# RF08b.net
KiCad netlist of a schematic drawn in EAGLE
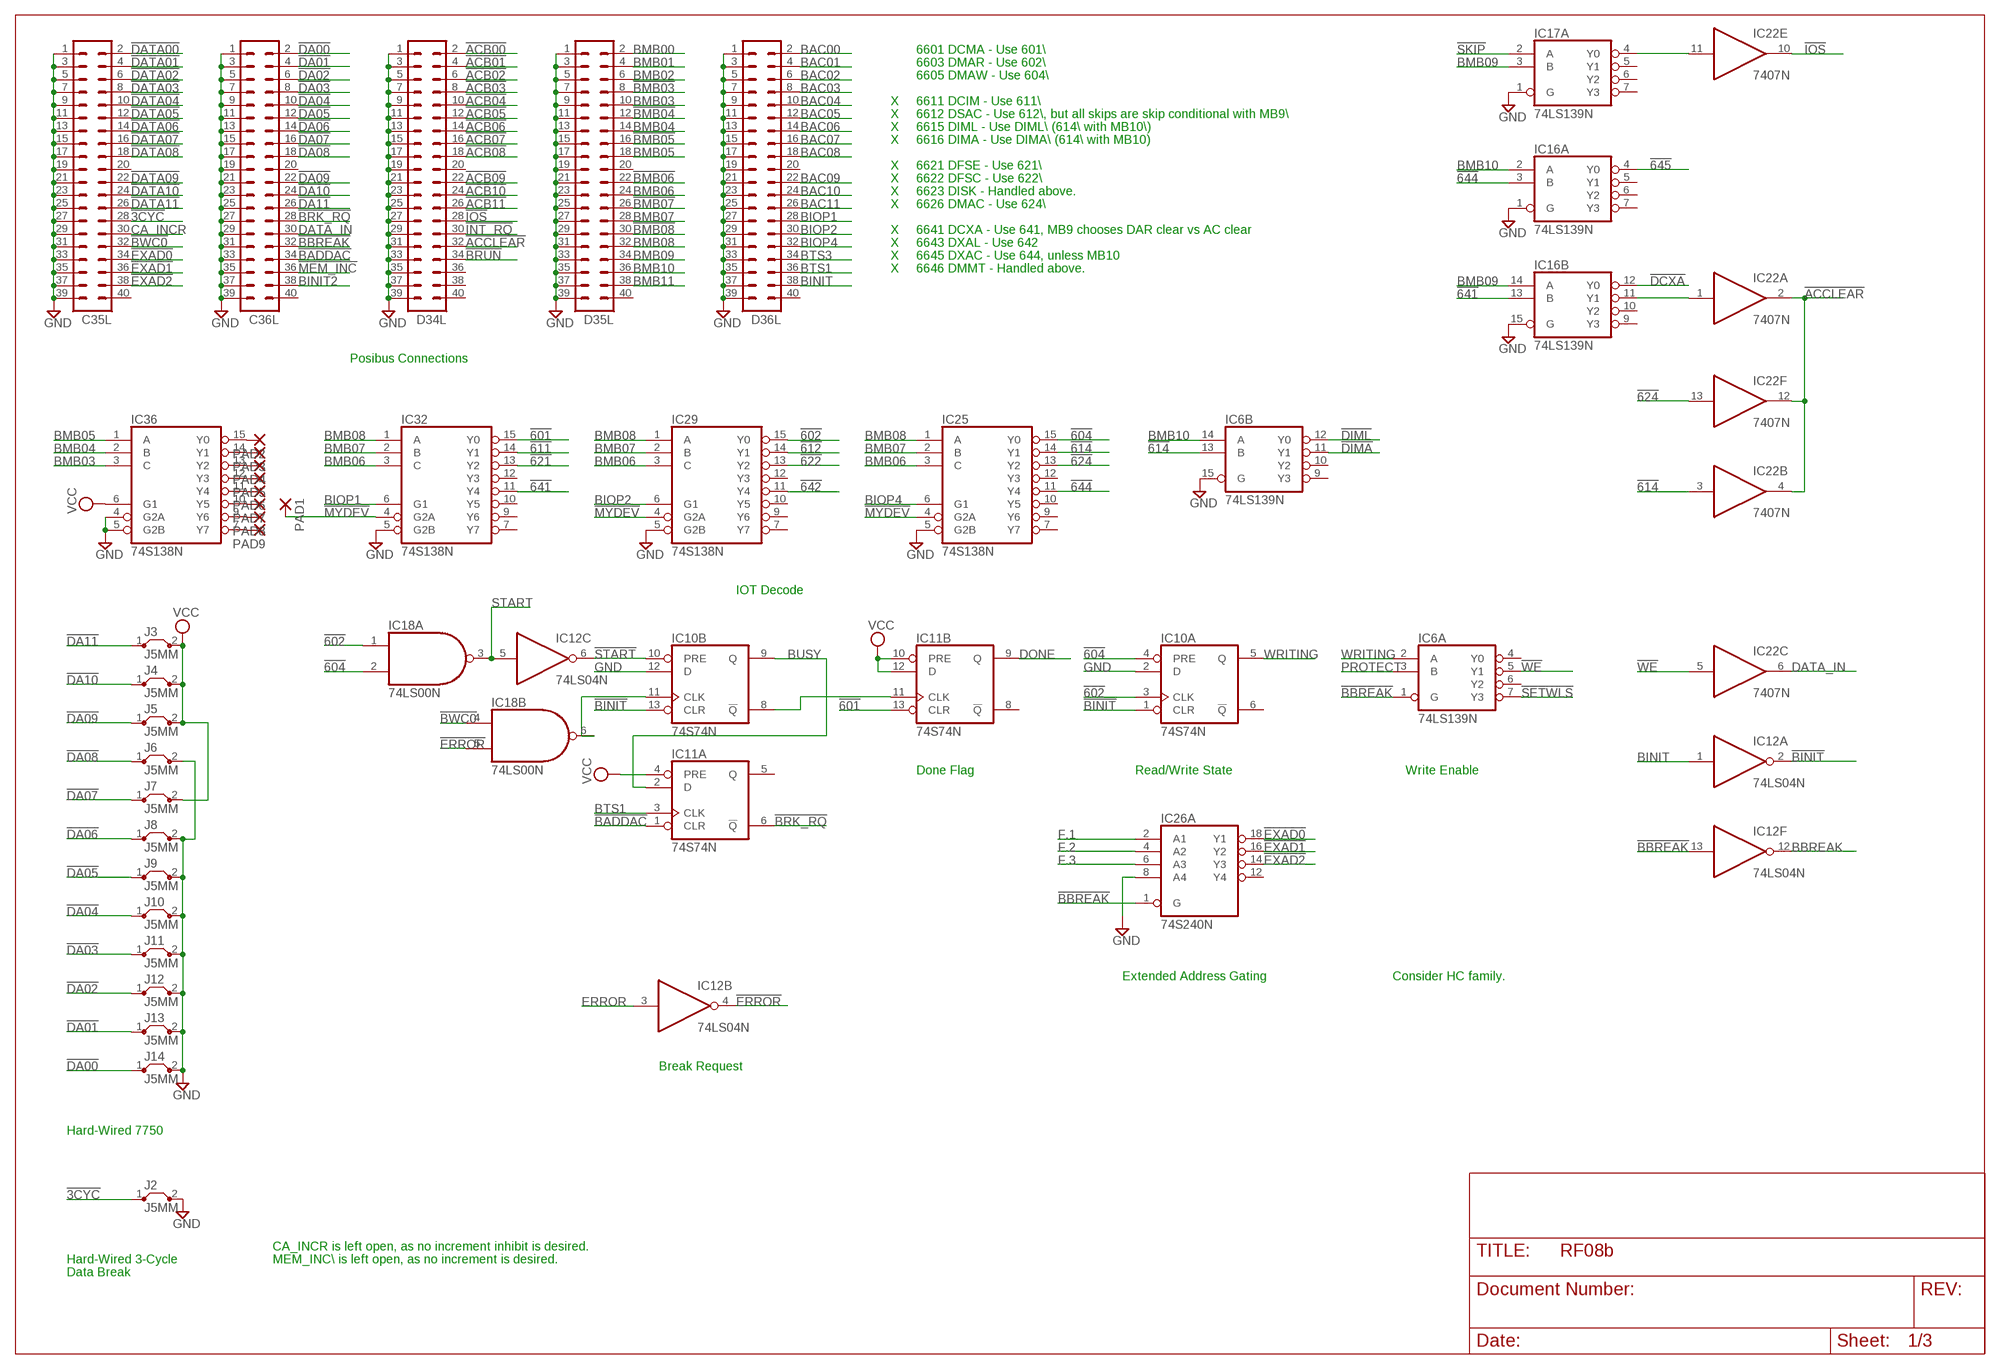
[diagram p0: schematic, sheet 1]
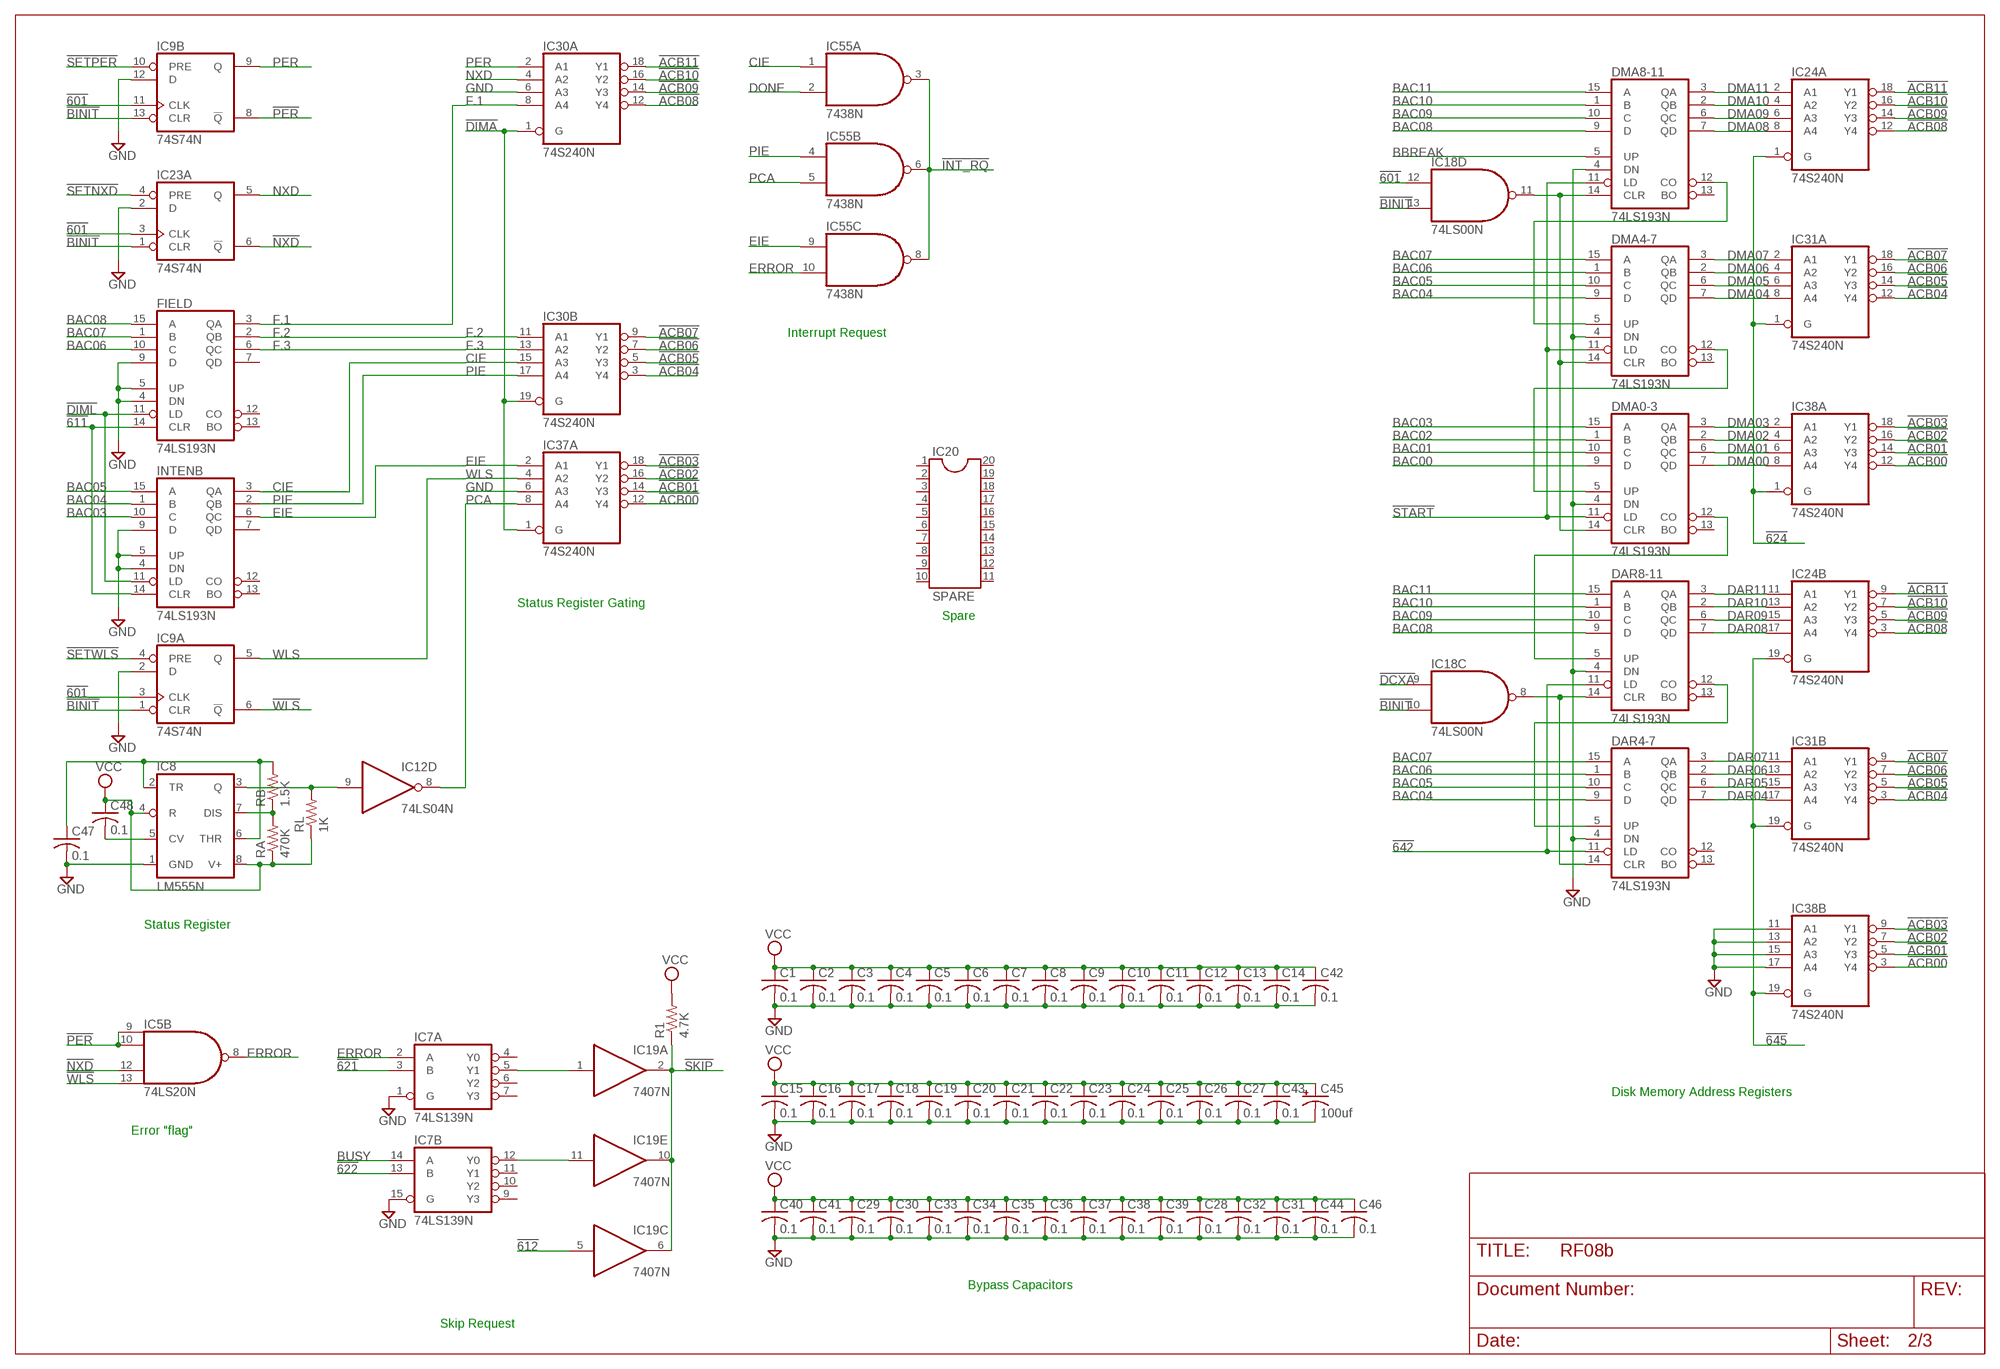
[diagram p1: schematic, sheet 2]
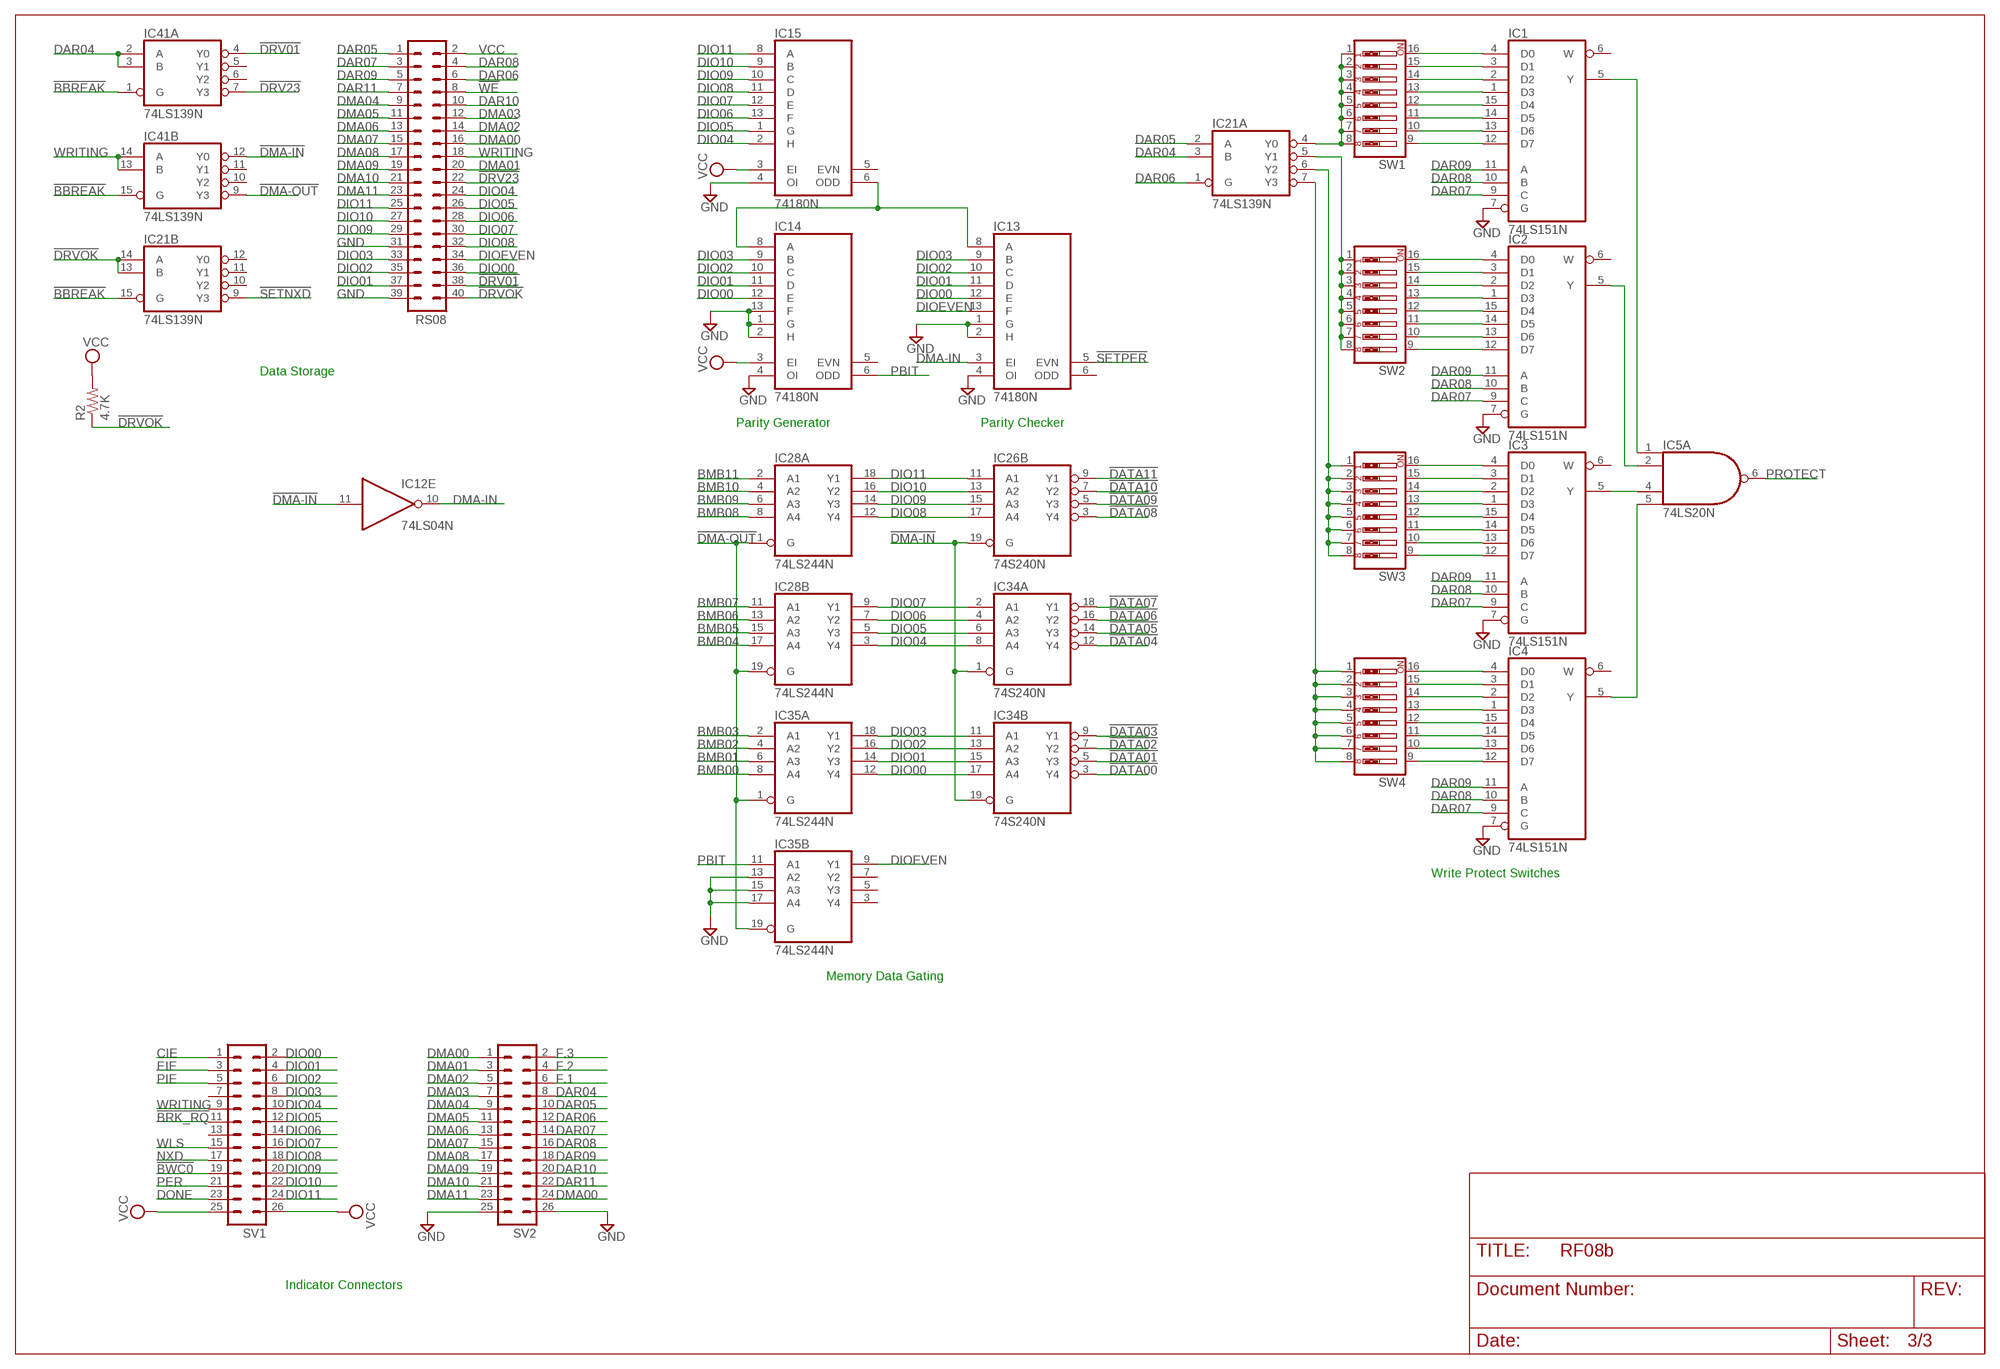
[diagram p2: schematic, sheet 3]

(export (version "E")
  (design (tool "Eeschema 10.0.6"))
  (components
    (comp (ref "C35L")
      (value "MA20-2")
      (footprint "eagle-import:MA20-2")
      (libsource (lib "eagle-import") (part "MA20-2"))
    )
    (comp (ref "C36L")
      (value "MA20-2")
      (footprint "eagle-import:MA20-2")
      (libsource (lib "eagle-import") (part "MA20-2"))
    )
    (comp (ref "D34L")
      (value "MA20-2")
      (footprint "eagle-import:MA20-2")
      (libsource (lib "eagle-import") (part "MA20-2"))
    )
    (comp (ref "D35L")
      (value "MA20-2")
      (footprint "eagle-import:MA20-2")
      (libsource (lib "eagle-import") (part "MA20-2"))
    )
    (comp (ref "D36L")
      (value "MA20-2")
      (footprint "eagle-import:MA20-2")
      (libsource (lib "eagle-import") (part "MA20-2"))
    )
    (comp (ref "IC6")
      (value "74LS139N")
      (footprint "eagle-import:DIL16")
      (libsource (lib "eagle-import") (part "74139NS"))
    )
    (comp (ref "IC10")
      (value "74S74N")
      (footprint "eagle-import:DIL14")
      (libsource (lib "eagle-import") (part "7474NS"))
    )
    (comp (ref "IC11")
      (value "74S74N")
      (footprint "eagle-import:DIL14")
      (libsource (lib "eagle-import") (part "7474NS"))
    )
    (comp (ref "IC12")
      (value "74LS04N")
      (footprint "eagle-import:DIL14")
      (libsource (lib "eagle-import") (part "7404NLS"))
    )
    (comp (ref "IC16")
      (value "74LS139N")
      (footprint "eagle-import:DIL16")
      (libsource (lib "eagle-import") (part "74139NS"))
    )
    (comp (ref "IC17")
      (value "74LS139N")
      (footprint "eagle-import:DIL16")
      (libsource (lib "eagle-import") (part "74139NS"))
    )
    (comp (ref "IC18")
      (value "74LS00N")
      (footprint "eagle-import:DIL14")
      (libsource (lib "eagle-import") (part "7400NLS"))
    )
    (comp (ref "IC22")
      (value "7407N")
      (footprint "eagle-import:DIL14")
      (libsource (lib "eagle-import") (part "7407N"))
    )
    (comp (ref "IC25")
      (value "74S138N")
      (footprint "eagle-import:DIL16")
      (libsource (lib "eagle-import") (part "74138NS"))
    )
    (comp (ref "IC26")
      (value "74S240N")
      (footprint "eagle-import:DIL20")
      (libsource (lib "eagle-import") (part "74240NS"))
    )
    (comp (ref "IC29")
      (value "74S138N")
      (footprint "eagle-import:DIL16")
      (libsource (lib "eagle-import") (part "74138NS"))
    )
    (comp (ref "IC32")
      (value "74S138N")
      (footprint "eagle-import:DIL16")
      (libsource (lib "eagle-import") (part "74138NS"))
    )
    (comp (ref "IC36")
      (value "74S138N")
      (footprint "eagle-import:DIL16")
      (libsource (lib "eagle-import") (part "74138NS"))
    )
    (comp (ref "J2")
      (value "J5MM")
      (footprint "eagle-import:05")
      (libsource (lib "eagle-import") (part "J5MM"))
    )
    (comp (ref "J3")
      (value "J5MM")
      (footprint "eagle-import:05")
      (libsource (lib "eagle-import") (part "J5MM"))
    )
    (comp (ref "J4")
      (value "J5MM")
      (footprint "eagle-import:05")
      (libsource (lib "eagle-import") (part "J5MM"))
    )
    (comp (ref "J5")
      (value "J5MM")
      (footprint "eagle-import:05")
      (libsource (lib "eagle-import") (part "J5MM"))
    )
    (comp (ref "J6")
      (value "J5MM")
      (footprint "eagle-import:05")
      (libsource (lib "eagle-import") (part "J5MM"))
    )
    (comp (ref "J7")
      (value "J5MM")
      (footprint "eagle-import:05")
      (libsource (lib "eagle-import") (part "J5MM"))
    )
    (comp (ref "J8")
      (value "J5MM")
      (footprint "eagle-import:05")
      (libsource (lib "eagle-import") (part "J5MM"))
    )
    (comp (ref "J9")
      (value "J5MM")
      (footprint "eagle-import:05")
      (libsource (lib "eagle-import") (part "J5MM"))
    )
    (comp (ref "J10")
      (value "J5MM")
      (footprint "eagle-import:05")
      (libsource (lib "eagle-import") (part "J5MM"))
    )
    (comp (ref "J11")
      (value "J5MM")
      (footprint "eagle-import:05")
      (libsource (lib "eagle-import") (part "J5MM"))
    )
    (comp (ref "J12")
      (value "J5MM")
      (footprint "eagle-import:05")
      (libsource (lib "eagle-import") (part "J5MM"))
    )
    (comp (ref "J13")
      (value "J5MM")
      (footprint "eagle-import:05")
      (libsource (lib "eagle-import") (part "J5MM"))
    )
    (comp (ref "J14")
      (value "J5MM")
      (footprint "eagle-import:05")
      (libsource (lib "eagle-import") (part "J5MM"))
    )
    (comp (ref "PAD1")
      (value "1,6/0,8")
      (footprint "eagle-import:1,6_0,8")
      (libsource (lib "eagle-import") (part "1,6/0,8"))
    )
    (comp (ref "PAD2")
      (value "1,6/0,8")
      (footprint "eagle-import:1,6_0,8")
      (libsource (lib "eagle-import") (part "1,6/0,8"))
    )
    (comp (ref "PAD3")
      (value "1,6/0,8")
      (footprint "eagle-import:1,6_0,8")
      (libsource (lib "eagle-import") (part "1,6/0,8"))
    )
    (comp (ref "PAD4")
      (value "1,6/0,8")
      (footprint "eagle-import:1,6_0,8")
      (libsource (lib "eagle-import") (part "1,6/0,8"))
    )
    (comp (ref "PAD5")
      (value "1,6/0,8")
      (footprint "eagle-import:1,6_0,8")
      (libsource (lib "eagle-import") (part "1,6/0,8"))
    )
    (comp (ref "PAD6")
      (value "1,6/0,8")
      (footprint "eagle-import:1,6_0,8")
      (libsource (lib "eagle-import") (part "1,6/0,8"))
    )
    (comp (ref "PAD7")
      (value "1,6/0,8")
      (footprint "eagle-import:1,6_0,8")
      (libsource (lib "eagle-import") (part "1,6/0,8"))
    )
    (comp (ref "PAD8")
      (value "1,6/0,8")
      (footprint "eagle-import:1,6_0,8")
      (libsource (lib "eagle-import") (part "1,6/0,8"))
    )
    (comp (ref "PAD9")
      (value "1,6/0,8")
      (footprint "eagle-import:1,6_0,8")
      (libsource (lib "eagle-import") (part "1,6/0,8"))
    )
    (comp (ref "C1")
      (value "0.1")
      (footprint "eagle-import:C050-025X075")
      (libsource (lib "eagle-import") (part "C-US050-025X075"))
    )
    (comp (ref "C2")
      (value "0.1")
      (footprint "eagle-import:C050-025X075")
      (libsource (lib "eagle-import") (part "C-US050-025X075"))
    )
    (comp (ref "C3")
      (value "0.1")
      (footprint "eagle-import:C050-025X075")
      (libsource (lib "eagle-import") (part "C-US050-025X075"))
    )
    (comp (ref "C4")
      (value "0.1")
      (footprint "eagle-import:C050-025X075")
      (libsource (lib "eagle-import") (part "C-US050-025X075"))
    )
    (comp (ref "C5")
      (value "0.1")
      (footprint "eagle-import:C050-025X075")
      (libsource (lib "eagle-import") (part "C-US050-025X075"))
    )
    (comp (ref "C6")
      (value "0.1")
      (footprint "eagle-import:C050-025X075")
      (libsource (lib "eagle-import") (part "C-US050-025X075"))
    )
    (comp (ref "C7")
      (value "0.1")
      (footprint "eagle-import:C050-025X075")
      (libsource (lib "eagle-import") (part "C-US050-025X075"))
    )
    (comp (ref "C8")
      (value "0.1")
      (footprint "eagle-import:C050-025X075")
      (libsource (lib "eagle-import") (part "C-US050-025X075"))
    )
    (comp (ref "C9")
      (value "0.1")
      (footprint "eagle-import:C050-025X075")
      (libsource (lib "eagle-import") (part "C-US050-025X075"))
    )
    (comp (ref "C10")
      (value "0.1")
      (footprint "eagle-import:C050-025X075")
      (libsource (lib "eagle-import") (part "C-US050-025X075"))
    )
    (comp (ref "C11")
      (value "0.1")
      (footprint "eagle-import:C050-025X075")
      (libsource (lib "eagle-import") (part "C-US050-025X075"))
    )
    (comp (ref "C12")
      (value "0.1")
      (footprint "eagle-import:C050-025X075")
      (libsource (lib "eagle-import") (part "C-US050-025X075"))
    )
    (comp (ref "C13")
      (value "0.1")
      (footprint "eagle-import:C050-025X075")
      (libsource (lib "eagle-import") (part "C-US050-025X075"))
    )
    (comp (ref "C14")
      (value "0.1")
      (footprint "eagle-import:C050-025X075")
      (libsource (lib "eagle-import") (part "C-US050-025X075"))
    )
    (comp (ref "C15")
      (value "0.1")
      (footprint "eagle-import:C050-025X075")
      (libsource (lib "eagle-import") (part "C-US050-025X075"))
    )
    (comp (ref "C16")
      (value "0.1")
      (footprint "eagle-import:C050-025X075")
      (libsource (lib "eagle-import") (part "C-US050-025X075"))
    )
    (comp (ref "C17")
      (value "0.1")
      (footprint "eagle-import:C050-025X075")
      (libsource (lib "eagle-import") (part "C-US050-025X075"))
    )
    (comp (ref "C18")
      (value "0.1")
      (footprint "eagle-import:C050-025X075")
      (libsource (lib "eagle-import") (part "C-US050-025X075"))
    )
    (comp (ref "C19")
      (value "0.1")
      (footprint "eagle-import:C050-025X075")
      (libsource (lib "eagle-import") (part "C-US050-025X075"))
    )
    (comp (ref "C20")
      (value "0.1")
      (footprint "eagle-import:C050-025X075")
      (libsource (lib "eagle-import") (part "C-US050-025X075"))
    )
    (comp (ref "C21")
      (value "0.1")
      (footprint "eagle-import:C050-025X075")
      (libsource (lib "eagle-import") (part "C-US050-025X075"))
    )
    (comp (ref "C22")
      (value "0.1")
      (footprint "eagle-import:C050-025X075")
      (libsource (lib "eagle-import") (part "C-US050-025X075"))
    )
    (comp (ref "C23")
      (value "0.1")
      (footprint "eagle-import:C050-025X075")
      (libsource (lib "eagle-import") (part "C-US050-025X075"))
    )
    (comp (ref "C24")
      (value "0.1")
      (footprint "eagle-import:C050-025X075")
      (libsource (lib "eagle-import") (part "C-US050-025X075"))
    )
    (comp (ref "C25")
      (value "0.1")
      (footprint "eagle-import:C050-025X075")
      (libsource (lib "eagle-import") (part "C-US050-025X075"))
    )
    (comp (ref "C26")
      (value "0.1")
      (footprint "eagle-import:C050-025X075")
      (libsource (lib "eagle-import") (part "C-US050-025X075"))
    )
    (comp (ref "C27")
      (value "0.1")
      (footprint "eagle-import:C050-025X075")
      (libsource (lib "eagle-import") (part "C-US050-025X075"))
    )
    (comp (ref "C28")
      (value "0.1")
      (footprint "eagle-import:C050-025X075")
      (libsource (lib "eagle-import") (part "C-US050-025X075"))
    )
    (comp (ref "C29")
      (value "0.1")
      (footprint "eagle-import:C050-025X075")
      (libsource (lib "eagle-import") (part "C-US050-025X075"))
    )
    (comp (ref "C30")
      (value "0.1")
      (footprint "eagle-import:C050-025X075")
      (libsource (lib "eagle-import") (part "C-US050-025X075"))
    )
    (comp (ref "C31")
      (value "0.1")
      (footprint "eagle-import:C050-025X075")
      (libsource (lib "eagle-import") (part "C-US050-025X075"))
    )
    (comp (ref "C32")
      (value "0.1")
      (footprint "eagle-import:C050-025X075")
      (libsource (lib "eagle-import") (part "C-US050-025X075"))
    )
    (comp (ref "C33")
      (value "0.1")
      (footprint "eagle-import:C050-025X075")
      (libsource (lib "eagle-import") (part "C-US050-025X075"))
    )
    (comp (ref "C34")
      (value "0.1")
      (footprint "eagle-import:C050-025X075")
      (libsource (lib "eagle-import") (part "C-US050-025X075"))
    )
    (comp (ref "C35")
      (value "0.1")
      (footprint "eagle-import:C050-025X075")
      (libsource (lib "eagle-import") (part "C-US050-025X075"))
    )
    (comp (ref "C36")
      (value "0.1")
      (footprint "eagle-import:C050-025X075")
      (libsource (lib "eagle-import") (part "C-US050-025X075"))
    )
    (comp (ref "C37")
      (value "0.1")
      (footprint "eagle-import:C050-025X075")
      (libsource (lib "eagle-import") (part "C-US050-025X075"))
    )
    (comp (ref "C38")
      (value "0.1")
      (footprint "eagle-import:C050-025X075")
      (libsource (lib "eagle-import") (part "C-US050-025X075"))
    )
    (comp (ref "C39")
      (value "0.1")
      (footprint "eagle-import:C050-025X075")
      (libsource (lib "eagle-import") (part "C-US050-025X075"))
    )
    (comp (ref "C40")
      (value "0.1")
      (footprint "eagle-import:C050-025X075")
      (libsource (lib "eagle-import") (part "C-US050-025X075"))
    )
    (comp (ref "C41")
      (value "0.1")
      (footprint "eagle-import:C050-025X075")
      (libsource (lib "eagle-import") (part "C-US050-025X075"))
    )
    (comp (ref "C42")
      (value "0.1")
      (footprint "eagle-import:C050-025X075")
      (libsource (lib "eagle-import") (part "C-US050-025X075"))
    )
    (comp (ref "C43")
      (value "0.1")
      (footprint "eagle-import:C050-025X075")
      (libsource (lib "eagle-import") (part "C-US050-025X075"))
    )
    (comp (ref "C44")
      (value "0.1")
      (footprint "eagle-import:C050-025X075")
      (libsource (lib "eagle-import") (part "C-US050-025X075"))
    )
    (comp (ref "C45")
      (value "100uf")
      (footprint "eagle-import:E22-6")
      (libsource (lib "eagle-import") (part "CPOL-USE22-6AXIAL"))
    )
    (comp (ref "C46")
      (value "0.1")
      (footprint "eagle-import:C050-025X075")
      (libsource (lib "eagle-import") (part "C-US050-025X075"))
    )
    (comp (ref "C47")
      (value "0.1")
      (footprint "eagle-import:C050-025X075")
      (libsource (lib "eagle-import") (part "C-US050-025X075"))
    )
    (comp (ref "C48")
      (value "0.1")
      (footprint "eagle-import:C050-025X075")
      (libsource (lib "eagle-import") (part "C-US050-025X075"))
    )
    (comp (ref "DAR4-7")
      (value "74LS193N")
      (footprint "eagle-import:DIL16")
      (libsource (lib "eagle-import") (part "74192NLS"))
    )
    (comp (ref "DAR8-11")
      (value "74LS193N")
      (footprint "eagle-import:DIL16")
      (libsource (lib "eagle-import") (part "74192NLS"))
    )
    (comp (ref "DMA0-3")
      (value "74LS193N")
      (footprint "eagle-import:DIL16")
      (libsource (lib "eagle-import") (part "74192NLS"))
    )
    (comp (ref "DMA4-7")
      (value "74LS193N")
      (footprint "eagle-import:DIL16")
      (libsource (lib "eagle-import") (part "74192NLS"))
    )
    (comp (ref "DMA8-11")
      (value "74LS193N")
      (footprint "eagle-import:DIL16")
      (libsource (lib "eagle-import") (part "74192NLS"))
    )
    (comp (ref "FIELD")
      (value "74LS193N")
      (footprint "eagle-import:DIL16")
      (libsource (lib "eagle-import") (part "74192NLS"))
    )
    (comp (ref "IC5")
      (value "74LS20N")
      (footprint "eagle-import:DIL14")
      (libsource (lib "eagle-import") (part "7420NLS"))
    )
    (comp (ref "IC7")
      (value "74LS139N")
      (footprint "eagle-import:DIL16")
      (libsource (lib "eagle-import") (part "74139NLS"))
    )
    (comp (ref "IC8")
      (value "LM555N")
      (footprint "eagle-import:DIL08")
      (libsource (lib "eagle-import") (part "555NLM"))
    )
    (comp (ref "IC9")
      (value "74S74N")
      (footprint "eagle-import:DIL14")
      (libsource (lib "eagle-import") (part "7474NS"))
    )
    (comp (ref "IC19")
      (value "7407N")
      (footprint "eagle-import:DIL14")
      (libsource (lib "eagle-import") (part "7407N"))
    )
    (comp (ref "IC20")
      (value "SPARE")
      (footprint "eagle-import:DIL20")
      (libsource (lib "eagle-import") (part "DIL20"))
    )
    (comp (ref "IC23")
      (value "74S74N")
      (footprint "eagle-import:DIL14")
      (libsource (lib "eagle-import") (part "7474NS"))
    )
    (comp (ref "IC24")
      (value "74S240N")
      (footprint "eagle-import:DIL20")
      (libsource (lib "eagle-import") (part "74240NS"))
    )
    (comp (ref "IC30")
      (value "74S240N")
      (footprint "eagle-import:DIL20")
      (libsource (lib "eagle-import") (part "74240NS"))
    )
    (comp (ref "IC31")
      (value "74S240N")
      (footprint "eagle-import:DIL20")
      (libsource (lib "eagle-import") (part "74240NS"))
    )
    (comp (ref "IC37")
      (value "74S240N")
      (footprint "eagle-import:DIL20")
      (libsource (lib "eagle-import") (part "74240NS"))
    )
    (comp (ref "IC38")
      (value "74S240N")
      (footprint "eagle-import:DIL20")
      (libsource (lib "eagle-import") (part "74240NS"))
    )
    (comp (ref "IC55")
      (value "7438N")
      (footprint "eagle-import:DIL14")
      (libsource (lib "eagle-import") (part "7438N"))
    )
    (comp (ref "INTENB")
      (value "74LS193N")
      (footprint "eagle-import:DIL16")
      (libsource (lib "eagle-import") (part "74192NLS"))
    )
    (comp (ref "R1")
      (value "4.7K")
      (footprint "eagle-import:0207_10")
      (libsource (lib "eagle-import") (part "R-US_0207/10"))
    )
    (comp (ref "RA")
      (value "470K")
      (footprint "eagle-import:0207_10")
      (libsource (lib "eagle-import") (part "R-US_0207/10"))
    )
    (comp (ref "RB")
      (value "1.5K")
      (footprint "eagle-import:0207_10")
      (libsource (lib "eagle-import") (part "R-US_0207/10"))
    )
    (comp (ref "RL")
      (value "1K")
      (footprint "eagle-import:0207_10")
      (libsource (lib "eagle-import") (part "R-US_0207/10"))
    )
    (comp (ref "IC1")
      (value "74LS151N")
      (footprint "eagle-import:DIL16")
      (libsource (lib "eagle-import") (part "74151NLS"))
    )
    (comp (ref "IC2")
      (value "74LS151N")
      (footprint "eagle-import:DIL16")
      (libsource (lib "eagle-import") (part "74151NLS"))
    )
    (comp (ref "IC3")
      (value "74LS151N")
      (footprint "eagle-import:DIL16")
      (libsource (lib "eagle-import") (part "74151NLS"))
    )
    (comp (ref "IC4")
      (value "74LS151N")
      (footprint "eagle-import:DIL16")
      (libsource (lib "eagle-import") (part "74151NLS"))
    )
    (comp (ref "IC13")
      (value "74180N")
      (footprint "eagle-import:DIL14")
      (libsource (lib "eagle-import") (part "74180N"))
    )
    (comp (ref "IC14")
      (value "74180N")
      (footprint "eagle-import:DIL14")
      (libsource (lib "eagle-import") (part "74180N"))
    )
    (comp (ref "IC15")
      (value "74180N")
      (footprint "eagle-import:DIL14")
      (libsource (lib "eagle-import") (part "74180N"))
    )
    (comp (ref "IC21")
      (value "74LS139N")
      (footprint "eagle-import:DIL16")
      (libsource (lib "eagle-import") (part "74139NLS"))
    )
    (comp (ref "IC28")
      (value "74LS244N")
      (footprint "eagle-import:DIL20")
      (libsource (lib "eagle-import") (part "74244NLS"))
    )
    (comp (ref "IC34")
      (value "74S240N")
      (footprint "eagle-import:DIL20")
      (libsource (lib "eagle-import") (part "74240NS"))
    )
    (comp (ref "IC35")
      (value "74LS244N")
      (footprint "eagle-import:DIL20")
      (libsource (lib "eagle-import") (part "74244NLS"))
    )
    (comp (ref "IC41")
      (value "74LS139N")
      (footprint "eagle-import:DIL16")
      (libsource (lib "eagle-import") (part "74139NLS"))
    )
    (comp (ref "R2")
      (value "4.7K")
      (footprint "eagle-import:0207_10")
      (libsource (lib "eagle-import") (part "R-US_0207/10"))
    )
    (comp (ref "RS08")
      (value "MA20-2")
      (footprint "eagle-import:MA20-2")
      (libsource (lib "eagle-import") (part "MA20-2"))
    )
    (comp (ref "SV1")
      (value "MA13-2")
      (footprint "eagle-import:MA13-2")
      (libsource (lib "eagle-import") (part "MA13-2"))
    )
    (comp (ref "SV2")
      (value "MA13-2")
      (footprint "eagle-import:MA13-2")
      (libsource (lib "eagle-import") (part "MA13-2"))
    )
    (comp (ref "SW1")
      (value "SW_DIP-8")
      (footprint "eagle-import:EDG-08")
      (libsource (lib "eagle-import") (part "SW_DIP-8"))
    )
    (comp (ref "SW2")
      (value "SW_DIP-8")
      (footprint "eagle-import:EDG-08")
      (libsource (lib "eagle-import") (part "SW_DIP-8"))
    )
    (comp (ref "SW3")
      (value "SW_DIP-8")
      (footprint "eagle-import:EDG-08")
      (libsource (lib "eagle-import") (part "SW_DIP-8"))
    )
    (comp (ref "SW4")
      (value "SW_DIP-8")
      (footprint "eagle-import:EDG-08")
      (libsource (lib "eagle-import") (part "SW_DIP-8"))
    )
  )
  (nets
    (net (code "1") (name "BAC00") (class "Default")
      (node (ref "D36L") (pin "2") (pinfunction "2_2") (pintype "passive"))
      (node (ref "DMA0-3") (pin "9") (pinfunction "D_9") (pintype "input"))
    )
    (net (code "2") (name "BAC01") (class "Default")
      (node (ref "D36L") (pin "4") (pinfunction "4_4") (pintype "passive"))
      (node (ref "DMA0-3") (pin "10") (pinfunction "C_10") (pintype "input"))
    )
    (net (code "3") (name "BAC02") (class "Default")
      (node (ref "D36L") (pin "6") (pinfunction "6_6") (pintype "passive"))
      (node (ref "DMA0-3") (pin "1") (pinfunction "B_1") (pintype "input"))
    )
    (net (code "4") (name "BAC03") (class "Default")
      (node (ref "D36L") (pin "8") (pinfunction "8_8") (pintype "passive"))
      (node (ref "DMA0-3") (pin "15") (pinfunction "A_15") (pintype "input"))
      (node (ref "INTENB") (pin "10") (pinfunction "C_10") (pintype "input"))
    )
    (net (code "5") (name "BAC04") (class "Default")
      (node (ref "D36L") (pin "10") (pinfunction "10_10") (pintype "passive"))
      (node (ref "DAR4-7") (pin "9") (pinfunction "D_9") (pintype "input"))
      (node (ref "DMA4-7") (pin "9") (pinfunction "D_9") (pintype "input"))
      (node (ref "INTENB") (pin "1") (pinfunction "B_1") (pintype "input"))
    )
    (net (code "6") (name "BAC05") (class "Default")
      (node (ref "D36L") (pin "12") (pinfunction "12_12") (pintype "passive"))
      (node (ref "DAR4-7") (pin "10") (pinfunction "C_10") (pintype "input"))
      (node (ref "DMA4-7") (pin "10") (pinfunction "C_10") (pintype "input"))
      (node (ref "INTENB") (pin "15") (pinfunction "A_15") (pintype "input"))
    )
    (net (code "7") (name "BAC06") (class "Default")
      (node (ref "D36L") (pin "14") (pinfunction "14_14") (pintype "passive"))
      (node (ref "DAR4-7") (pin "1") (pinfunction "B_1") (pintype "input"))
      (node (ref "DMA4-7") (pin "1") (pinfunction "B_1") (pintype "input"))
      (node (ref "FIELD") (pin "10") (pinfunction "C_10") (pintype "input"))
    )
    (net (code "8") (name "BAC07") (class "Default")
      (node (ref "D36L") (pin "16") (pinfunction "16_16") (pintype "passive"))
      (node (ref "DAR4-7") (pin "15") (pinfunction "A_15") (pintype "input"))
      (node (ref "DMA4-7") (pin "15") (pinfunction "A_15") (pintype "input"))
      (node (ref "FIELD") (pin "1") (pinfunction "B_1") (pintype "input"))
    )
    (net (code "9") (name "BAC08") (class "Default")
      (node (ref "D36L") (pin "18") (pinfunction "18_18") (pintype "passive"))
      (node (ref "DAR8-11") (pin "9") (pinfunction "D_9") (pintype "input"))
      (node (ref "DMA8-11") (pin "9") (pinfunction "D_9") (pintype "input"))
      (node (ref "FIELD") (pin "15") (pinfunction "A_15") (pintype "input"))
    )
    (net (code "10") (name "BAC09") (class "Default")
      (node (ref "D36L") (pin "22") (pinfunction "22_22") (pintype "passive"))
      (node (ref "DAR8-11") (pin "10") (pinfunction "C_10") (pintype "input"))
      (node (ref "DMA8-11") (pin "10") (pinfunction "C_10") (pintype "input"))
    )
    (net (code "11") (name "BAC10") (class "Default")
      (node (ref "D36L") (pin "24") (pinfunction "24_24") (pintype "passive"))
      (node (ref "DAR8-11") (pin "1") (pinfunction "B_1") (pintype "input"))
      (node (ref "DMA8-11") (pin "1") (pinfunction "B_1") (pintype "input"))
    )
    (net (code "12") (name "BAC11") (class "Default")
      (node (ref "D36L") (pin "26") (pinfunction "26_26") (pintype "passive"))
      (node (ref "DAR8-11") (pin "15") (pinfunction "A_15") (pintype "input"))
      (node (ref "DMA8-11") (pin "15") (pinfunction "A_15") (pintype "input"))
    )
    (net (code "13") (name "BBREAK") (class "Default")
      (node (ref "DMA8-11") (pin "5") (pinfunction "UP_5") (pintype "input"))
      (node (ref "IC12") (pin "12") (pinfunction "O_12") (pintype "output"))
    )
    (net (code "14") (name "BINIT") (class "Default")
      (node (ref "D36L") (pin "38") (pinfunction "38_38") (pintype "passive"))
      (node (ref "IC12") (pin "1") (pinfunction "I_1") (pintype "input"))
    )
    (net (code "15") (name "BINIT2") (class "Default")
      (node (ref "C36L") (pin "38") (pinfunction "38_38") (pintype "passive"))
    )
    (net (code "16") (name "BIOP1") (class "Default")
      (node (ref "D36L") (pin "28") (pinfunction "28_28") (pintype "passive"))
      (node (ref "IC32") (pin "6") (pinfunction "G1_6") (pintype "input"))
    )
    (net (code "17") (name "BIOP2") (class "Default")
      (node (ref "D36L") (pin "30") (pinfunction "30_30") (pintype "passive"))
      (node (ref "IC29") (pin "6") (pinfunction "G1_6") (pintype "input"))
    )
    (net (code "18") (name "BIOP4") (class "Default")
      (node (ref "D36L") (pin "32") (pinfunction "32_32") (pintype "passive"))
      (node (ref "IC25") (pin "6") (pinfunction "G1_6") (pintype "input"))
    )
    (net (code "19") (name "BMB00") (class "Default")
      (node (ref "D35L") (pin "2") (pinfunction "2_2") (pintype "passive"))
      (node (ref "IC35") (pin "8") (pinfunction "A4_8") (pintype "input"))
    )
    (net (code "20") (name "BMB01") (class "Default")
      (node (ref "D35L") (pin "4") (pinfunction "4_4") (pintype "passive"))
      (node (ref "IC35") (pin "6") (pinfunction "A3_6") (pintype "input"))
    )
    (net (code "21") (name "BMB02") (class "Default")
      (node (ref "D35L") (pin "6") (pinfunction "6_6") (pintype "passive"))
      (node (ref "IC35") (pin "4") (pinfunction "A2_4") (pintype "input"))
    )
    (net (code "22") (name "BMB03") (class "Default")
      (node (ref "D35L") (pin "10") (pinfunction "10_10") (pintype "passive"))
      (node (ref "IC35") (pin "2") (pinfunction "A1_2") (pintype "input"))
      (node (ref "IC36") (pin "3") (pinfunction "C_3") (pintype "input"))
    )
    (net (code "23") (name "BMB04") (class "Default")
      (node (ref "D35L") (pin "14") (pinfunction "14_14") (pintype "passive"))
      (node (ref "IC28") (pin "17") (pinfunction "A4_17") (pintype "input"))
      (node (ref "IC36") (pin "2") (pinfunction "B_2") (pintype "input"))
    )
    (net (code "24") (name "BMB05") (class "Default")
      (node (ref "D35L") (pin "18") (pinfunction "18_18") (pintype "passive"))
      (node (ref "IC28") (pin "15") (pinfunction "A3_15") (pintype "input"))
      (node (ref "IC36") (pin "1") (pinfunction "A_1") (pintype "input"))
    )
    (net (code "25") (name "BMB06") (class "Default")
      (node (ref "D35L") (pin "24") (pinfunction "24_24") (pintype "passive"))
      (node (ref "IC25") (pin "3") (pinfunction "C_3") (pintype "input"))
      (node (ref "IC28") (pin "13") (pinfunction "A2_13") (pintype "input"))
      (node (ref "IC29") (pin "3") (pinfunction "C_3") (pintype "input"))
      (node (ref "IC32") (pin "3") (pinfunction "C_3") (pintype "input"))
    )
    (net (code "26") (name "BMB07") (class "Default")
      (node (ref "D35L") (pin "28") (pinfunction "28_28") (pintype "passive"))
      (node (ref "IC25") (pin "2") (pinfunction "B_2") (pintype "input"))
      (node (ref "IC28") (pin "11") (pinfunction "A1_11") (pintype "input"))
      (node (ref "IC29") (pin "2") (pinfunction "B_2") (pintype "input"))
      (node (ref "IC32") (pin "2") (pinfunction "B_2") (pintype "input"))
    )
    (net (code "27") (name "BMB08") (class "Default")
      (node (ref "D35L") (pin "32") (pinfunction "32_32") (pintype "passive"))
      (node (ref "IC25") (pin "1") (pinfunction "A_1") (pintype "input"))
      (node (ref "IC28") (pin "8") (pinfunction "A4_8") (pintype "input"))
      (node (ref "IC29") (pin "1") (pinfunction "A_1") (pintype "input"))
      (node (ref "IC32") (pin "1") (pinfunction "A_1") (pintype "input"))
    )
    (net (code "28") (name "BMB09") (class "Default")
      (node (ref "D35L") (pin "34") (pinfunction "34_34") (pintype "passive"))
      (node (ref "IC16") (pin "14") (pinfunction "A_14") (pintype "input"))
      (node (ref "IC17") (pin "3") (pinfunction "B_3") (pintype "input"))
      (node (ref "IC28") (pin "6") (pinfunction "A3_6") (pintype "input"))
    )
    (net (code "29") (name "BMB10") (class "Default")
      (node (ref "D35L") (pin "36") (pinfunction "36_36") (pintype "passive"))
      (node (ref "IC16") (pin "2") (pinfunction "A_2") (pintype "input"))
      (node (ref "IC28") (pin "4") (pinfunction "A2_4") (pintype "input"))
      (node (ref "IC6") (pin "14") (pinfunction "A_14") (pintype "input"))
    )
    (net (code "30") (name "BMB11") (class "Default")
      (node (ref "D35L") (pin "38") (pinfunction "38_38") (pintype "passive"))
      (node (ref "IC28") (pin "2") (pinfunction "A1_2") (pintype "input"))
    )
    (net (code "31") (name "BTS1") (class "Default")
      (node (ref "D36L") (pin "36") (pinfunction "36_36") (pintype "passive"))
      (node (ref "IC11") (pin "3") (pinfunction "CLK_3") (pintype "input"))
    )
    (net (code "32") (name "BTS3") (class "Default")
      (node (ref "D36L") (pin "34") (pinfunction "34_34") (pintype "passive"))
    )
    (net (code "33") (name "BUSY") (class "Default")
      (node (ref "IC10") (pin "9") (pinfunction "Q_9") (pintype "output"))
      (node (ref "IC11") (pin "2") (pinfunction "D_2") (pintype "input"))
      (node (ref "IC7") (pin "14") (pinfunction "A_14") (pintype "input"))
    )
    (net (code "34") (name "CA_INCR") (class "Default")
      (node (ref "C35L") (pin "30") (pinfunction "30_30") (pintype "passive"))
    )
    (net (code "35") (name "CIE") (class "Default")
      (node (ref "IC30") (pin "15") (pinfunction "A3_15") (pintype "input"))
      (node (ref "IC55") (pin "1") (pinfunction "I0_1") (pintype "input"))
      (node (ref "INTENB") (pin "3") (pinfunction "QA_3") (pintype "output"))
      (node (ref "SV1") (pin "1") (pinfunction "1_1") (pintype "passive"))
    )
    (net (code "36") (name "DAR04") (class "Default")
      (node (ref "DAR4-7") (pin "7") (pinfunction "QD_7") (pintype "output"))
      (node (ref "IC21") (pin "3") (pinfunction "B_3") (pintype "input"))
      (node (ref "IC31") (pin "17") (pinfunction "A4_17") (pintype "input"))
      (node (ref "IC41") (pin "2") (pinfunction "A_2") (pintype "input"))
      (node (ref "IC41") (pin "3") (pinfunction "B_3") (pintype "input"))
      (node (ref "SV2") (pin "8") (pinfunction "8_8") (pintype "passive"))
    )
    (net (code "37") (name "DAR05") (class "Default")
      (node (ref "DAR4-7") (pin "6") (pinfunction "QC_6") (pintype "output"))
      (node (ref "IC21") (pin "2") (pinfunction "A_2") (pintype "input"))
      (node (ref "IC31") (pin "15") (pinfunction "A3_15") (pintype "input"))
      (node (ref "RS08") (pin "1") (pinfunction "1_1") (pintype "passive"))
      (node (ref "SV2") (pin "10") (pinfunction "10_10") (pintype "passive"))
    )
    (net (code "38") (name "DAR06") (class "Default")
      (node (ref "DAR4-7") (pin "2") (pinfunction "QB_2") (pintype "output"))
      (node (ref "IC21") (pin "1") (pinfunction "G_1") (pintype "input"))
      (node (ref "IC31") (pin "13") (pinfunction "A2_13") (pintype "input"))
      (node (ref "RS08") (pin "6") (pinfunction "6_6") (pintype "passive"))
      (node (ref "SV2") (pin "12") (pinfunction "12_12") (pintype "passive"))
    )
    (net (code "39") (name "DAR07") (class "Default")
      (node (ref "DAR4-7") (pin "3") (pinfunction "QA_3") (pintype "output"))
      (node (ref "IC1") (pin "9") (pinfunction "C_9") (pintype "input"))
      (node (ref "IC2") (pin "9") (pinfunction "C_9") (pintype "input"))
      (node (ref "IC3") (pin "9") (pinfunction "C_9") (pintype "input"))
      (node (ref "IC31") (pin "11") (pinfunction "A1_11") (pintype "input"))
      (node (ref "IC4") (pin "9") (pinfunction "C_9") (pintype "input"))
      (node (ref "RS08") (pin "3") (pinfunction "3_3") (pintype "passive"))
      (node (ref "SV2") (pin "14") (pinfunction "14_14") (pintype "passive"))
    )
    (net (code "40") (name "DAR08") (class "Default")
      (node (ref "DAR8-11") (pin "7") (pinfunction "QD_7") (pintype "output"))
      (node (ref "IC1") (pin "10") (pinfunction "B_10") (pintype "input"))
      (node (ref "IC2") (pin "10") (pinfunction "B_10") (pintype "input"))
      (node (ref "IC24") (pin "17") (pinfunction "A4_17") (pintype "input"))
      (node (ref "IC3") (pin "10") (pinfunction "B_10") (pintype "input"))
      (node (ref "IC4") (pin "10") (pinfunction "B_10") (pintype "input"))
      (node (ref "RS08") (pin "4") (pinfunction "4_4") (pintype "passive"))
      (node (ref "SV2") (pin "16") (pinfunction "16_16") (pintype "passive"))
    )
    (net (code "41") (name "DAR09") (class "Default")
      (node (ref "DAR8-11") (pin "6") (pinfunction "QC_6") (pintype "output"))
      (node (ref "IC1") (pin "11") (pinfunction "A_11") (pintype "input"))
      (node (ref "IC2") (pin "11") (pinfunction "A_11") (pintype "input"))
      (node (ref "IC24") (pin "15") (pinfunction "A3_15") (pintype "input"))
      (node (ref "IC3") (pin "11") (pinfunction "A_11") (pintype "input"))
      (node (ref "IC4") (pin "11") (pinfunction "A_11") (pintype "input"))
      (node (ref "RS08") (pin "5") (pinfunction "5_5") (pintype "passive"))
      (node (ref "SV2") (pin "18") (pinfunction "18_18") (pintype "passive"))
    )
    (net (code "42") (name "DAR10") (class "Default")
      (node (ref "DAR8-11") (pin "2") (pinfunction "QB_2") (pintype "output"))
      (node (ref "IC24") (pin "13") (pinfunction "A2_13") (pintype "input"))
      (node (ref "RS08") (pin "10") (pinfunction "10_10") (pintype "passive"))
      (node (ref "SV2") (pin "20") (pinfunction "20_20") (pintype "passive"))
    )
    (net (code "43") (name "DAR11") (class "Default")
      (node (ref "DAR8-11") (pin "3") (pinfunction "QA_3") (pintype "output"))
      (node (ref "IC24") (pin "11") (pinfunction "A1_11") (pintype "input"))
      (node (ref "RS08") (pin "7") (pinfunction "7_7") (pintype "passive"))
      (node (ref "SV2") (pin "22") (pinfunction "22_22") (pintype "passive"))
    )
    (net (code "44") (name "DATA_IN") (class "Default")
      (node (ref "C36L") (pin "30") (pinfunction "30_30") (pintype "passive"))
      (node (ref "IC22") (pin "6") (pinfunction "O_6") (pintype "open_collector"))
    )
    (net (code "45") (name "DIO00") (class "Default")
      (node (ref "IC13") (pin "12") (pinfunction "E_12") (pintype "input"))
      (node (ref "IC14") (pin "12") (pinfunction "E_12") (pintype "input"))
      (node (ref "IC34") (pin "17") (pinfunction "A4_17") (pintype "input"))
      (node (ref "IC35") (pin "12") (pinfunction "Y4_12") (pintype "tri_state"))
      (node (ref "RS08") (pin "36") (pinfunction "36_36") (pintype "passive"))
      (node (ref "SV1") (pin "2") (pinfunction "2_2") (pintype "passive"))
    )
    (net (code "46") (name "DIO01") (class "Default")
      (node (ref "IC13") (pin "11") (pinfunction "D_11") (pintype "input"))
      (node (ref "IC14") (pin "11") (pinfunction "D_11") (pintype "input"))
      (node (ref "IC34") (pin "15") (pinfunction "A3_15") (pintype "input"))
      (node (ref "IC35") (pin "14") (pinfunction "Y3_14") (pintype "tri_state"))
      (node (ref "RS08") (pin "37") (pinfunction "37_37") (pintype "passive"))
      (node (ref "SV1") (pin "4") (pinfunction "4_4") (pintype "passive"))
    )
    (net (code "47") (name "DIO02") (class "Default")
      (node (ref "IC13") (pin "10") (pinfunction "C_10") (pintype "input"))
      (node (ref "IC14") (pin "10") (pinfunction "C_10") (pintype "input"))
      (node (ref "IC34") (pin "13") (pinfunction "A2_13") (pintype "input"))
      (node (ref "IC35") (pin "16") (pinfunction "Y2_16") (pintype "tri_state"))
      (node (ref "RS08") (pin "35") (pinfunction "35_35") (pintype "passive"))
      (node (ref "SV1") (pin "6") (pinfunction "6_6") (pintype "passive"))
    )
    (net (code "48") (name "DIO03") (class "Default")
      (node (ref "IC13") (pin "9") (pinfunction "B_9") (pintype "input"))
      (node (ref "IC14") (pin "9") (pinfunction "B_9") (pintype "input"))
      (node (ref "IC34") (pin "11") (pinfunction "A1_11") (pintype "input"))
      (node (ref "IC35") (pin "18") (pinfunction "Y1_18") (pintype "tri_state"))
      (node (ref "RS08") (pin "33") (pinfunction "33_33") (pintype "passive"))
      (node (ref "SV1") (pin "8") (pinfunction "8_8") (pintype "passive"))
    )
    (net (code "49") (name "DIO04") (class "Default")
      (node (ref "IC15") (pin "2") (pinfunction "H_2") (pintype "input"))
      (node (ref "IC28") (pin "3") (pinfunction "Y4_3") (pintype "tri_state"))
      (node (ref "IC34") (pin "8") (pinfunction "A4_8") (pintype "input"))
      (node (ref "RS08") (pin "24") (pinfunction "24_24") (pintype "passive"))
      (node (ref "SV1") (pin "10") (pinfunction "10_10") (pintype "passive"))
    )
    (net (code "50") (name "DIO05") (class "Default")
      (node (ref "IC15") (pin "1") (pinfunction "G_1") (pintype "input"))
      (node (ref "IC28") (pin "5") (pinfunction "Y3_5") (pintype "tri_state"))
      (node (ref "IC34") (pin "6") (pinfunction "A3_6") (pintype "input"))
      (node (ref "RS08") (pin "26") (pinfunction "26_26") (pintype "passive"))
      (node (ref "SV1") (pin "12") (pinfunction "12_12") (pintype "passive"))
    )
    (net (code "51") (name "DIO06") (class "Default")
      (node (ref "IC15") (pin "13") (pinfunction "F_13") (pintype "input"))
      (node (ref "IC28") (pin "7") (pinfunction "Y2_7") (pintype "tri_state"))
      (node (ref "IC34") (pin "4") (pinfunction "A2_4") (pintype "input"))
      (node (ref "RS08") (pin "28") (pinfunction "28_28") (pintype "passive"))
      (node (ref "SV1") (pin "14") (pinfunction "14_14") (pintype "passive"))
    )
    (net (code "52") (name "DIO07") (class "Default")
      (node (ref "IC15") (pin "12") (pinfunction "E_12") (pintype "input"))
      (node (ref "IC28") (pin "9") (pinfunction "Y1_9") (pintype "tri_state"))
      (node (ref "IC34") (pin "2") (pinfunction "A1_2") (pintype "input"))
      (node (ref "RS08") (pin "30") (pinfunction "30_30") (pintype "passive"))
      (node (ref "SV1") (pin "16") (pinfunction "16_16") (pintype "passive"))
    )
    (net (code "53") (name "DIO08") (class "Default")
      (node (ref "IC15") (pin "11") (pinfunction "D_11") (pintype "input"))
      (node (ref "IC26") (pin "17") (pinfunction "A4_17") (pintype "input"))
      (node (ref "IC28") (pin "12") (pinfunction "Y4_12") (pintype "tri_state"))
      (node (ref "RS08") (pin "32") (pinfunction "32_32") (pintype "passive"))
      (node (ref "SV1") (pin "18") (pinfunction "18_18") (pintype "passive"))
    )
    (net (code "54") (name "DIO09") (class "Default")
      (node (ref "IC15") (pin "10") (pinfunction "C_10") (pintype "input"))
      (node (ref "IC26") (pin "15") (pinfunction "A3_15") (pintype "input"))
      (node (ref "IC28") (pin "14") (pinfunction "Y3_14") (pintype "tri_state"))
      (node (ref "RS08") (pin "29") (pinfunction "29_29") (pintype "passive"))
      (node (ref "SV1") (pin "20") (pinfunction "20_20") (pintype "passive"))
    )
    (net (code "55") (name "DIO10") (class "Default")
      (node (ref "IC15") (pin "9") (pinfunction "B_9") (pintype "input"))
      (node (ref "IC26") (pin "13") (pinfunction "A2_13") (pintype "input"))
      (node (ref "IC28") (pin "16") (pinfunction "Y2_16") (pintype "tri_state"))
      (node (ref "RS08") (pin "27") (pinfunction "27_27") (pintype "passive"))
      (node (ref "SV1") (pin "22") (pinfunction "22_22") (pintype "passive"))
    )
    (net (code "56") (name "DIO11") (class "Default")
      (node (ref "IC15") (pin "8") (pinfunction "A_8") (pintype "input"))
      (node (ref "IC26") (pin "11") (pinfunction "A1_11") (pintype "input"))
      (node (ref "IC28") (pin "18") (pinfunction "Y1_18") (pintype "tri_state"))
      (node (ref "RS08") (pin "25") (pinfunction "25_25") (pintype "passive"))
      (node (ref "SV1") (pin "24") (pinfunction "24_24") (pintype "passive"))
    )
    (net (code "57") (name "DIOEVEN") (class "Default")
      (node (ref "IC13") (pin "13") (pinfunction "F_13") (pintype "input"))
      (node (ref "IC35") (pin "9") (pinfunction "Y1_9") (pintype "tri_state"))
      (node (ref "RS08") (pin "34") (pinfunction "34_34") (pintype "passive"))
    )
    (net (code "58") (name "DMA-IN") (class "Default")
      (node (ref "IC12") (pin "10") (pinfunction "O_10") (pintype "output"))
      (node (ref "IC13") (pin "3") (pinfunction "EI_3") (pintype "input"))
    )
    (net (code "59") (name "DMA00") (class "Default")
      (node (ref "DMA0-3") (pin "7") (pinfunction "QD_7") (pintype "output"))
      (node (ref "IC38") (pin "8") (pinfunction "A4_8") (pintype "input"))
      (node (ref "RS08") (pin "16") (pinfunction "16_16") (pintype "passive"))
      (node (ref "SV2") (pin "1") (pinfunction "1_1") (pintype "passive"))
      (node (ref "SV2") (pin "24") (pinfunction "24_24") (pintype "passive"))
    )
    (net (code "60") (name "DMA01") (class "Default")
      (node (ref "DMA0-3") (pin "6") (pinfunction "QC_6") (pintype "output"))
      (node (ref "IC38") (pin "6") (pinfunction "A3_6") (pintype "input"))
      (node (ref "RS08") (pin "20") (pinfunction "20_20") (pintype "passive"))
      (node (ref "SV2") (pin "3") (pinfunction "3_3") (pintype "passive"))
    )
    (net (code "61") (name "DMA02") (class "Default")
      (node (ref "DMA0-3") (pin "2") (pinfunction "QB_2") (pintype "output"))
      (node (ref "IC38") (pin "4") (pinfunction "A2_4") (pintype "input"))
      (node (ref "RS08") (pin "14") (pinfunction "14_14") (pintype "passive"))
      (node (ref "SV2") (pin "5") (pinfunction "5_5") (pintype "passive"))
    )
    (net (code "62") (name "DMA03") (class "Default")
      (node (ref "DMA0-3") (pin "3") (pinfunction "QA_3") (pintype "output"))
      (node (ref "IC38") (pin "2") (pinfunction "A1_2") (pintype "input"))
      (node (ref "RS08") (pin "12") (pinfunction "12_12") (pintype "passive"))
      (node (ref "SV2") (pin "7") (pinfunction "7_7") (pintype "passive"))
    )
    (net (code "63") (name "DMA04") (class "Default")
      (node (ref "DMA4-7") (pin "7") (pinfunction "QD_7") (pintype "output"))
      (node (ref "IC31") (pin "8") (pinfunction "A4_8") (pintype "input"))
      (node (ref "RS08") (pin "9") (pinfunction "9_9") (pintype "passive"))
      (node (ref "SV2") (pin "9") (pinfunction "9_9") (pintype "passive"))
    )
    (net (code "64") (name "DMA05") (class "Default")
      (node (ref "DMA4-7") (pin "6") (pinfunction "QC_6") (pintype "output"))
      (node (ref "IC31") (pin "6") (pinfunction "A3_6") (pintype "input"))
      (node (ref "RS08") (pin "11") (pinfunction "11_11") (pintype "passive"))
      (node (ref "SV2") (pin "11") (pinfunction "11_11") (pintype "passive"))
    )
    (net (code "65") (name "DMA06") (class "Default")
      (node (ref "DMA4-7") (pin "2") (pinfunction "QB_2") (pintype "output"))
      (node (ref "IC31") (pin "4") (pinfunction "A2_4") (pintype "input"))
      (node (ref "RS08") (pin "13") (pinfunction "13_13") (pintype "passive"))
      (node (ref "SV2") (pin "13") (pinfunction "13_13") (pintype "passive"))
    )
    (net (code "66") (name "DMA07") (class "Default")
      (node (ref "DMA4-7") (pin "3") (pinfunction "QA_3") (pintype "output"))
      (node (ref "IC31") (pin "2") (pinfunction "A1_2") (pintype "input"))
      (node (ref "RS08") (pin "15") (pinfunction "15_15") (pintype "passive"))
      (node (ref "SV2") (pin "15") (pinfunction "15_15") (pintype "passive"))
    )
    (net (code "67") (name "DMA08") (class "Default")
      (node (ref "DMA8-11") (pin "7") (pinfunction "QD_7") (pintype "output"))
      (node (ref "IC24") (pin "8") (pinfunction "A4_8") (pintype "input"))
      (node (ref "RS08") (pin "17") (pinfunction "17_17") (pintype "passive"))
      (node (ref "SV2") (pin "17") (pinfunction "17_17") (pintype "passive"))
    )
    (net (code "68") (name "DMA09") (class "Default")
      (node (ref "DMA8-11") (pin "6") (pinfunction "QC_6") (pintype "output"))
      (node (ref "IC24") (pin "6") (pinfunction "A3_6") (pintype "input"))
      (node (ref "RS08") (pin "19") (pinfunction "19_19") (pintype "passive"))
      (node (ref "SV2") (pin "19") (pinfunction "19_19") (pintype "passive"))
    )
    (net (code "69") (name "DMA10") (class "Default")
      (node (ref "DMA8-11") (pin "2") (pinfunction "QB_2") (pintype "output"))
      (node (ref "IC24") (pin "4") (pinfunction "A2_4") (pintype "input"))
      (node (ref "RS08") (pin "21") (pinfunction "21_21") (pintype "passive"))
      (node (ref "SV2") (pin "21") (pinfunction "21_21") (pintype "passive"))
    )
    (net (code "70") (name "DMA11") (class "Default")
      (node (ref "DMA8-11") (pin "3") (pinfunction "QA_3") (pintype "output"))
      (node (ref "IC24") (pin "2") (pinfunction "A1_2") (pintype "input"))
      (node (ref "RS08") (pin "23") (pinfunction "23_23") (pintype "passive"))
      (node (ref "SV2") (pin "23") (pinfunction "23_23") (pintype "passive"))
    )
    (net (code "71") (name "DONE") (class "Default")
      (node (ref "IC11") (pin "9") (pinfunction "Q_9") (pintype "output"))
      (node (ref "IC55") (pin "2") (pinfunction "I1_2") (pintype "input"))
      (node (ref "SV1") (pin "23") (pinfunction "23_23") (pintype "passive"))
    )
    (net (code "72") (name "EIE") (class "Default")
      (node (ref "IC37") (pin "2") (pinfunction "A1_2") (pintype "input"))
      (node (ref "IC55") (pin "9") (pinfunction "I0_9") (pintype "input"))
      (node (ref "INTENB") (pin "6") (pinfunction "QC_6") (pintype "output"))
      (node (ref "SV1") (pin "3") (pinfunction "3_3") (pintype "passive"))
    )
    (net (code "73") (name "ERROR") (class "Default")
      (node (ref "IC12") (pin "3") (pinfunction "I_3") (pintype "input"))
      (node (ref "IC5") (pin "8") (pinfunction "O_8") (pintype "output"))
      (node (ref "IC55") (pin "10") (pinfunction "I1_10") (pintype "input"))
      (node (ref "IC7") (pin "2") (pinfunction "A_2") (pintype "input"))
    )
    (net (code "74") (name "F.1") (class "Default")
      (node (ref "FIELD") (pin "3") (pinfunction "QA_3") (pintype "output"))
      (node (ref "IC26") (pin "2") (pinfunction "A1_2") (pintype "input"))
      (node (ref "IC30") (pin "8") (pinfunction "A4_8") (pintype "input"))
      (node (ref "SV2") (pin "6") (pinfunction "6_6") (pintype "passive"))
    )
    (net (code "75") (name "F.2") (class "Default")
      (node (ref "FIELD") (pin "2") (pinfunction "QB_2") (pintype "output"))
      (node (ref "IC26") (pin "4") (pinfunction "A2_4") (pintype "input"))
      (node (ref "IC30") (pin "11") (pinfunction "A1_11") (pintype "input"))
      (node (ref "SV2") (pin "4") (pinfunction "4_4") (pintype "passive"))
    )
    (net (code "76") (name "F.3") (class "Default")
      (node (ref "FIELD") (pin "6") (pinfunction "QC_6") (pintype "output"))
      (node (ref "IC26") (pin "6") (pinfunction "A3_6") (pintype "input"))
      (node (ref "IC30") (pin "13") (pinfunction "A2_13") (pintype "input"))
      (node (ref "SV2") (pin "2") (pinfunction "2_2") (pintype "passive"))
    )
    (net (code "77") (name "GND") (class "Default")
      (node (ref "C1") (pin "2") (pinfunction "2_2") (pintype "passive"))
      (node (ref "C10") (pin "2") (pinfunction "2_2") (pintype "passive"))
      (node (ref "C11") (pin "2") (pinfunction "2_2") (pintype "passive"))
      (node (ref "C12") (pin "2") (pinfunction "2_2") (pintype "passive"))
      (node (ref "C13") (pin "2") (pinfunction "2_2") (pintype "passive"))
      (node (ref "C14") (pin "2") (pinfunction "2_2") (pintype "passive"))
      (node (ref "C15") (pin "2") (pinfunction "2_2") (pintype "passive"))
      (node (ref "C16") (pin "2") (pinfunction "2_2") (pintype "passive"))
      (node (ref "C17") (pin "2") (pinfunction "2_2") (pintype "passive"))
      (node (ref "C18") (pin "2") (pinfunction "2_2") (pintype "passive"))
      (node (ref "C19") (pin "2") (pinfunction "2_2") (pintype "passive"))
      (node (ref "C2") (pin "2") (pinfunction "2_2") (pintype "passive"))
      (node (ref "C20") (pin "2") (pinfunction "2_2") (pintype "passive"))
      (node (ref "C21") (pin "2") (pinfunction "2_2") (pintype "passive"))
      (node (ref "C22") (pin "2") (pinfunction "2_2") (pintype "passive"))
      (node (ref "C23") (pin "2") (pinfunction "2_2") (pintype "passive"))
      (node (ref "C24") (pin "2") (pinfunction "2_2") (pintype "passive"))
      (node (ref "C25") (pin "2") (pinfunction "2_2") (pintype "passive"))
      (node (ref "C26") (pin "2") (pinfunction "2_2") (pintype "passive"))
      (node (ref "C27") (pin "2") (pinfunction "2_2") (pintype "passive"))
      (node (ref "C28") (pin "2") (pinfunction "2_2") (pintype "passive"))
      (node (ref "C29") (pin "2") (pinfunction "2_2") (pintype "passive"))
      (node (ref "C3") (pin "2") (pinfunction "2_2") (pintype "passive"))
      (node (ref "C30") (pin "2") (pinfunction "2_2") (pintype "passive"))
      (node (ref "C31") (pin "2") (pinfunction "2_2") (pintype "passive"))
      (node (ref "C32") (pin "2") (pinfunction "2_2") (pintype "passive"))
      (node (ref "C33") (pin "2") (pinfunction "2_2") (pintype "passive"))
      (node (ref "C34") (pin "2") (pinfunction "2_2") (pintype "passive"))
      (node (ref "C35") (pin "2") (pinfunction "2_2") (pintype "passive"))
      (node (ref "C35L") (pin "1") (pinfunction "1_1") (pintype "passive"))
      (node (ref "C35L") (pin "11") (pinfunction "11_11") (pintype "passive"))
      (node (ref "C35L") (pin "13") (pinfunction "13_13") (pintype "passive"))
      (node (ref "C35L") (pin "15") (pinfunction "15_15") (pintype "passive"))
      (node (ref "C35L") (pin "17") (pinfunction "17_17") (pintype "passive"))
      (node (ref "C35L") (pin "19") (pinfunction "19_19") (pintype "passive"))
      (node (ref "C35L") (pin "21") (pinfunction "21_21") (pintype "passive"))
      (node (ref "C35L") (pin "23") (pinfunction "23_23") (pintype "passive"))
      (node (ref "C35L") (pin "25") (pinfunction "25_25") (pintype "passive"))
      (node (ref "C35L") (pin "27") (pinfunction "27_27") (pintype "passive"))
      (node (ref "C35L") (pin "29") (pinfunction "29_29") (pintype "passive"))
      (node (ref "C35L") (pin "3") (pinfunction "3_3") (pintype "passive"))
      (node (ref "C35L") (pin "31") (pinfunction "31_31") (pintype "passive"))
      (node (ref "C35L") (pin "33") (pinfunction "33_33") (pintype "passive"))
      (node (ref "C35L") (pin "35") (pinfunction "35_35") (pintype "passive"))
      (node (ref "C35L") (pin "37") (pinfunction "37_37") (pintype "passive"))
      (node (ref "C35L") (pin "39") (pinfunction "39_39") (pintype "passive"))
      (node (ref "C35L") (pin "5") (pinfunction "5_5") (pintype "passive"))
      (node (ref "C35L") (pin "7") (pinfunction "7_7") (pintype "passive"))
      (node (ref "C35L") (pin "9") (pinfunction "9_9") (pintype "passive"))
      (node (ref "C36") (pin "2") (pinfunction "2_2") (pintype "passive"))
      (node (ref "C36L") (pin "1") (pinfunction "1_1") (pintype "passive"))
      (node (ref "C36L") (pin "11") (pinfunction "11_11") (pintype "passive"))
      (node (ref "C36L") (pin "13") (pinfunction "13_13") (pintype "passive"))
      (node (ref "C36L") (pin "15") (pinfunction "15_15") (pintype "passive"))
      (node (ref "C36L") (pin "17") (pinfunction "17_17") (pintype "passive"))
      (node (ref "C36L") (pin "19") (pinfunction "19_19") (pintype "passive"))
      (node (ref "C36L") (pin "21") (pinfunction "21_21") (pintype "passive"))
      (node (ref "C36L") (pin "23") (pinfunction "23_23") (pintype "passive"))
      (node (ref "C36L") (pin "25") (pinfunction "25_25") (pintype "passive"))
      (node (ref "C36L") (pin "27") (pinfunction "27_27") (pintype "passive"))
      (node (ref "C36L") (pin "29") (pinfunction "29_29") (pintype "passive"))
      (node (ref "C36L") (pin "3") (pinfunction "3_3") (pintype "passive"))
      (node (ref "C36L") (pin "31") (pinfunction "31_31") (pintype "passive"))
      (node (ref "C36L") (pin "33") (pinfunction "33_33") (pintype "passive"))
      (node (ref "C36L") (pin "35") (pinfunction "35_35") (pintype "passive"))
      (node (ref "C36L") (pin "37") (pinfunction "37_37") (pintype "passive"))
      (node (ref "C36L") (pin "39") (pinfunction "39_39") (pintype "passive"))
      (node (ref "C36L") (pin "5") (pinfunction "5_5") (pintype "passive"))
      (node (ref "C36L") (pin "7") (pinfunction "7_7") (pintype "passive"))
      (node (ref "C36L") (pin "9") (pinfunction "9_9") (pintype "passive"))
      (node (ref "C37") (pin "2") (pinfunction "2_2") (pintype "passive"))
      (node (ref "C38") (pin "2") (pinfunction "2_2") (pintype "passive"))
      (node (ref "C39") (pin "2") (pinfunction "2_2") (pintype "passive"))
      (node (ref "C4") (pin "2") (pinfunction "2_2") (pintype "passive"))
      (node (ref "C40") (pin "2") (pinfunction "2_2") (pintype "passive"))
      (node (ref "C41") (pin "2") (pinfunction "2_2") (pintype "passive"))
      (node (ref "C42") (pin "2") (pinfunction "2_2") (pintype "passive"))
      (node (ref "C43") (pin "2") (pinfunction "2_2") (pintype "passive"))
      (node (ref "C44") (pin "2") (pinfunction "2_2") (pintype "passive"))
      (node (ref "C45") (pin "-") (pinfunction "-_-") (pintype "passive"))
      (node (ref "C46") (pin "2") (pinfunction "2_2") (pintype "passive"))
      (node (ref "C47") (pin "2") (pinfunction "2_2") (pintype "passive"))
      (node (ref "C5") (pin "2") (pinfunction "2_2") (pintype "passive"))
      (node (ref "C6") (pin "2") (pinfunction "2_2") (pintype "passive"))
      (node (ref "C7") (pin "2") (pinfunction "2_2") (pintype "passive"))
      (node (ref "C8") (pin "2") (pinfunction "2_2") (pintype "passive"))
      (node (ref "C9") (pin "2") (pinfunction "2_2") (pintype "passive"))
      (node (ref "D34L") (pin "1") (pinfunction "1_1") (pintype "passive"))
      (node (ref "D34L") (pin "11") (pinfunction "11_11") (pintype "passive"))
      (node (ref "D34L") (pin "13") (pinfunction "13_13") (pintype "passive"))
      (node (ref "D34L") (pin "15") (pinfunction "15_15") (pintype "passive"))
      (node (ref "D34L") (pin "17") (pinfunction "17_17") (pintype "passive"))
      (node (ref "D34L") (pin "19") (pinfunction "19_19") (pintype "passive"))
      (node (ref "D34L") (pin "21") (pinfunction "21_21") (pintype "passive"))
      (node (ref "D34L") (pin "23") (pinfunction "23_23") (pintype "passive"))
      (node (ref "D34L") (pin "25") (pinfunction "25_25") (pintype "passive"))
      (node (ref "D34L") (pin "27") (pinfunction "27_27") (pintype "passive"))
      (node (ref "D34L") (pin "29") (pinfunction "29_29") (pintype "passive"))
      (node (ref "D34L") (pin "3") (pinfunction "3_3") (pintype "passive"))
      (node (ref "D34L") (pin "31") (pinfunction "31_31") (pintype "passive"))
      (node (ref "D34L") (pin "33") (pinfunction "33_33") (pintype "passive"))
      (node (ref "D34L") (pin "35") (pinfunction "35_35") (pintype "passive"))
      (node (ref "D34L") (pin "37") (pinfunction "37_37") (pintype "passive"))
      (node (ref "D34L") (pin "39") (pinfunction "39_39") (pintype "passive"))
      (node (ref "D34L") (pin "5") (pinfunction "5_5") (pintype "passive"))
      (node (ref "D34L") (pin "7") (pinfunction "7_7") (pintype "passive"))
      (node (ref "D34L") (pin "9") (pinfunction "9_9") (pintype "passive"))
      (node (ref "D35L") (pin "1") (pinfunction "1_1") (pintype "passive"))
      (node (ref "D35L") (pin "11") (pinfunction "11_11") (pintype "passive"))
      (node (ref "D35L") (pin "13") (pinfunction "13_13") (pintype "passive"))
      (node (ref "D35L") (pin "15") (pinfunction "15_15") (pintype "passive"))
      (node (ref "D35L") (pin "17") (pinfunction "17_17") (pintype "passive"))
      (node (ref "D35L") (pin "19") (pinfunction "19_19") (pintype "passive"))
      (node (ref "D35L") (pin "21") (pinfunction "21_21") (pintype "passive"))
      (node (ref "D35L") (pin "23") (pinfunction "23_23") (pintype "passive"))
      (node (ref "D35L") (pin "25") (pinfunction "25_25") (pintype "passive"))
      (node (ref "D35L") (pin "27") (pinfunction "27_27") (pintype "passive"))
      (node (ref "D35L") (pin "29") (pinfunction "29_29") (pintype "passive"))
      (node (ref "D35L") (pin "3") (pinfunction "3_3") (pintype "passive"))
      (node (ref "D35L") (pin "31") (pinfunction "31_31") (pintype "passive"))
      (node (ref "D35L") (pin "33") (pinfunction "33_33") (pintype "passive"))
      (node (ref "D35L") (pin "35") (pinfunction "35_35") (pintype "passive"))
      (node (ref "D35L") (pin "37") (pinfunction "37_37") (pintype "passive"))
      (node (ref "D35L") (pin "39") (pinfunction "39_39") (pintype "passive"))
      (node (ref "D35L") (pin "5") (pinfunction "5_5") (pintype "passive"))
      (node (ref "D35L") (pin "7") (pinfunction "7_7") (pintype "passive"))
      (node (ref "D35L") (pin "9") (pinfunction "9_9") (pintype "passive"))
      (node (ref "D36L") (pin "1") (pinfunction "1_1") (pintype "passive"))
      (node (ref "D36L") (pin "11") (pinfunction "11_11") (pintype "passive"))
      (node (ref "D36L") (pin "13") (pinfunction "13_13") (pintype "passive"))
      (node (ref "D36L") (pin "15") (pinfunction "15_15") (pintype "passive"))
      (node (ref "D36L") (pin "17") (pinfunction "17_17") (pintype "passive"))
      (node (ref "D36L") (pin "19") (pinfunction "19_19") (pintype "passive"))
      (node (ref "D36L") (pin "21") (pinfunction "21_21") (pintype "passive"))
      (node (ref "D36L") (pin "23") (pinfunction "23_23") (pintype "passive"))
      (node (ref "D36L") (pin "25") (pinfunction "25_25") (pintype "passive"))
      (node (ref "D36L") (pin "27") (pinfunction "27_27") (pintype "passive"))
      (node (ref "D36L") (pin "29") (pinfunction "29_29") (pintype "passive"))
      (node (ref "D36L") (pin "3") (pinfunction "3_3") (pintype "passive"))
      (node (ref "D36L") (pin "31") (pinfunction "31_31") (pintype "passive"))
      (node (ref "D36L") (pin "33") (pinfunction "33_33") (pintype "passive"))
      (node (ref "D36L") (pin "35") (pinfunction "35_35") (pintype "passive"))
      (node (ref "D36L") (pin "37") (pinfunction "37_37") (pintype "passive"))
      (node (ref "D36L") (pin "39") (pinfunction "39_39") (pintype "passive"))
      (node (ref "D36L") (pin "5") (pinfunction "5_5") (pintype "passive"))
      (node (ref "D36L") (pin "7") (pinfunction "7_7") (pintype "passive"))
      (node (ref "D36L") (pin "9") (pinfunction "9_9") (pintype "passive"))
      (node (ref "DAR4-7") (pin "4") (pinfunction "DN_4") (pintype "input"))
      (node (ref "DAR8-11") (pin "4") (pinfunction "DN_4") (pintype "input"))
      (node (ref "DMA0-3") (pin "4") (pinfunction "DN_4") (pintype "input"))
      (node (ref "DMA4-7") (pin "4") (pinfunction "DN_4") (pintype "input"))
      (node (ref "DMA8-11") (pin "4") (pinfunction "DN_4") (pintype "input"))
      (node (ref "FIELD") (pin "4") (pinfunction "DN_4") (pintype "input"))
      (node (ref "FIELD") (pin "5") (pinfunction "UP_5") (pintype "input"))
      (node (ref "FIELD") (pin "9") (pinfunction "D_9") (pintype "input"))
      (node (ref "IC1") (pin "7") (pinfunction "G_7") (pintype "input"))
      (node (ref "IC10") (pin "12") (pinfunction "D_12") (pintype "input"))
      (node (ref "IC10") (pin "2") (pinfunction "D_2") (pintype "input"))
      (node (ref "IC13") (pin "1") (pinfunction "G_1") (pintype "input"))
      (node (ref "IC13") (pin "2") (pinfunction "H_2") (pintype "input"))
      (node (ref "IC13") (pin "4") (pinfunction "OI_4") (pintype "input"))
      (node (ref "IC14") (pin "1") (pinfunction "G_1") (pintype "input"))
      (node (ref "IC14") (pin "13") (pinfunction "F_13") (pintype "input"))
      (node (ref "IC14") (pin "2") (pinfunction "H_2") (pintype "input"))
      (node (ref "IC14") (pin "4") (pinfunction "OI_4") (pintype "input"))
      (node (ref "IC15") (pin "4") (pinfunction "OI_4") (pintype "input"))
      (node (ref "IC16") (pin "1") (pinfunction "G_1") (pintype "input"))
      (node (ref "IC16") (pin "15") (pinfunction "G_15") (pintype "input"))
      (node (ref "IC17") (pin "1") (pinfunction "G_1") (pintype "input"))
      (node (ref "IC2") (pin "7") (pinfunction "G_7") (pintype "input"))
      (node (ref "IC23") (pin "2") (pinfunction "D_2") (pintype "input"))
      (node (ref "IC25") (pin "5") (pinfunction "G2B_5") (pintype "input"))
      (node (ref "IC26") (pin "8") (pinfunction "A4_8") (pintype "input"))
      (node (ref "IC29") (pin "5") (pinfunction "G2B_5") (pintype "input"))
      (node (ref "IC3") (pin "7") (pinfunction "G_7") (pintype "input"))
      (node (ref "IC30") (pin "6") (pinfunction "A3_6") (pintype "input"))
      (node (ref "IC32") (pin "5") (pinfunction "G2B_5") (pintype "input"))
      (node (ref "IC35") (pin "13") (pinfunction "A2_13") (pintype "input"))
      (node (ref "IC35") (pin "15") (pinfunction "A3_15") (pintype "input"))
      (node (ref "IC35") (pin "17") (pinfunction "A4_17") (pintype "input"))
      (node (ref "IC36") (pin "4") (pinfunction "G2A_4") (pintype "input"))
      (node (ref "IC36") (pin "5") (pinfunction "G2B_5") (pintype "input"))
      (node (ref "IC37") (pin "6") (pinfunction "A3_6") (pintype "input"))
      (node (ref "IC38") (pin "11") (pinfunction "A1_11") (pintype "input"))
      (node (ref "IC38") (pin "13") (pinfunction "A2_13") (pintype "input"))
      (node (ref "IC38") (pin "15") (pinfunction "A3_15") (pintype "input"))
      (node (ref "IC38") (pin "17") (pinfunction "A4_17") (pintype "input"))
      (node (ref "IC4") (pin "7") (pinfunction "G_7") (pintype "input"))
      (node (ref "IC6") (pin "15") (pinfunction "G_15") (pintype "input"))
      (node (ref "IC7") (pin "1") (pinfunction "G_1") (pintype "input"))
      (node (ref "IC7") (pin "15") (pinfunction "G_15") (pintype "input"))
      (node (ref "IC8") (pin "1") (pinfunction "GND_1") (pintype "power_in"))
      (node (ref "IC9") (pin "12") (pinfunction "D_12") (pintype "input"))
      (node (ref "IC9") (pin "2") (pinfunction "D_2") (pintype "input"))
      (node (ref "INTENB") (pin "4") (pinfunction "DN_4") (pintype "input"))
      (node (ref "INTENB") (pin "5") (pinfunction "UP_5") (pintype "input"))
      (node (ref "INTENB") (pin "9") (pinfunction "D_9") (pintype "input"))
      (node (ref "J10") (pin "2") (pinfunction "2_2") (pintype "passive"))
      (node (ref "J11") (pin "2") (pinfunction "2_2") (pintype "passive"))
      (node (ref "J12") (pin "2") (pinfunction "2_2") (pintype "passive"))
      (node (ref "J13") (pin "2") (pinfunction "2_2") (pintype "passive"))
      (node (ref "J14") (pin "2") (pinfunction "2_2") (pintype "passive"))
      (node (ref "J2") (pin "2") (pinfunction "2_2") (pintype "passive"))
      (node (ref "J6") (pin "2") (pinfunction "2_2") (pintype "passive"))
      (node (ref "J8") (pin "2") (pinfunction "2_2") (pintype "passive"))
      (node (ref "J9") (pin "2") (pinfunction "2_2") (pintype "passive"))
      (node (ref "RS08") (pin "31") (pinfunction "31_31") (pintype "passive"))
      (node (ref "RS08") (pin "39") (pinfunction "39_39") (pintype "passive"))
      (node (ref "SV2") (pin "25") (pinfunction "25_25") (pintype "passive"))
      (node (ref "SV2") (pin "26") (pinfunction "26_26") (pintype "passive"))
    )
    (net (code "78") (name "NXD") (class "Default")
      (node (ref "IC23") (pin "5") (pinfunction "Q_5") (pintype "output"))
      (node (ref "IC30") (pin "4") (pinfunction "A2_4") (pintype "input"))
      (node (ref "SV1") (pin "17") (pinfunction "17_17") (pintype "passive"))
    )
    (net (code "79") (name "Net-(DAR4-7A-CLR)") (class "Default")
      (node (ref "DAR4-7") (pin "14") (pinfunction "CLR_14") (pintype "input"))
      (node (ref "DAR8-11") (pin "14") (pinfunction "CLR_14") (pintype "input"))
      (node (ref "IC18") (pin "8") (pinfunction "O_8") (pintype "output"))
    )
    (net (code "80") (name "Net-(DAR4-7A-UP)") (class "Default")
      (node (ref "DAR4-7") (pin "5") (pinfunction "UP_5") (pintype "input"))
      (node (ref "DAR8-11") (pin "12") (pinfunction "CO_12") (pintype "output"))
    )
    (net (code "81") (name "Net-(DAR8-11A-UP)") (class "Default")
      (node (ref "DAR8-11") (pin "5") (pinfunction "UP_5") (pintype "input"))
      (node (ref "DMA0-3") (pin "12") (pinfunction "CO_12") (pintype "output"))
    )
    (net (code "82") (name "Net-(DMA0-3A-CLR)") (class "Default")
      (node (ref "DMA0-3") (pin "14") (pinfunction "CLR_14") (pintype "input"))
      (node (ref "DMA4-7") (pin "14") (pinfunction "CLR_14") (pintype "input"))
      (node (ref "DMA8-11") (pin "14") (pinfunction "CLR_14") (pintype "input"))
      (node (ref "IC18") (pin "11") (pinfunction "O_11") (pintype "output"))
    )
    (net (code "83") (name "Net-(DMA0-3A-UP)") (class "Default")
      (node (ref "DMA0-3") (pin "5") (pinfunction "UP_5") (pintype "input"))
      (node (ref "DMA4-7") (pin "12") (pinfunction "CO_12") (pintype "output"))
    )
    (net (code "84") (name "Net-(DMA4-7A-UP)") (class "Default")
      (node (ref "DMA4-7") (pin "5") (pinfunction "UP_5") (pintype "input"))
      (node (ref "DMA8-11") (pin "12") (pinfunction "CO_12") (pintype "output"))
    )
    (net (code "85") (name "Net-(IC1A-D0)") (class "Default")
      (node (ref "IC1") (pin "4") (pinfunction "D0_4") (pintype "input"))
      (node (ref "SW1") (pin "16") (pinfunction "16_16") (pintype "passive"))
    )
    (net (code "86") (name "Net-(IC1A-D1)") (class "Default")
      (node (ref "IC1") (pin "3") (pinfunction "D1_3") (pintype "input"))
      (node (ref "SW1") (pin "15") (pinfunction "15_15") (pintype "passive"))
    )
    (net (code "87") (name "Net-(IC1A-D2)") (class "Default")
      (node (ref "IC1") (pin "2") (pinfunction "D2_2") (pintype "input"))
      (node (ref "SW1") (pin "14") (pinfunction "14_14") (pintype "passive"))
    )
    (net (code "88") (name "Net-(IC1A-D3)") (class "Default")
      (node (ref "IC1") (pin "1") (pinfunction "D3_1") (pintype "input"))
      (node (ref "SW1") (pin "13") (pinfunction "13_13") (pintype "passive"))
    )
    (net (code "89") (name "Net-(IC1A-D4)") (class "Default")
      (node (ref "IC1") (pin "15") (pinfunction "D4_15") (pintype "input"))
      (node (ref "SW1") (pin "12") (pinfunction "12_12") (pintype "passive"))
    )
    (net (code "90") (name "Net-(IC1A-D5)") (class "Default")
      (node (ref "IC1") (pin "14") (pinfunction "D5_14") (pintype "input"))
      (node (ref "SW1") (pin "11") (pinfunction "11_11") (pintype "passive"))
    )
    (net (code "91") (name "Net-(IC1A-D6)") (class "Default")
      (node (ref "IC1") (pin "13") (pinfunction "D6_13") (pintype "input"))
      (node (ref "SW1") (pin "10") (pinfunction "10_10") (pintype "passive"))
    )
    (net (code "92") (name "Net-(IC1A-D7)") (class "Default")
      (node (ref "IC1") (pin "12") (pinfunction "D7_12") (pintype "input"))
      (node (ref "SW1") (pin "9") (pinfunction "9_9") (pintype "passive"))
    )
    (net (code "93") (name "Net-(IC1A-Y)") (class "Default")
      (node (ref "IC1") (pin "5") (pinfunction "Y_5") (pintype "output"))
      (node (ref "IC5") (pin "1") (pinfunction "I0_1") (pintype "input"))
    )
    (net (code "94") (name "Net-(IC2A-D0)") (class "Default")
      (node (ref "IC2") (pin "4") (pinfunction "D0_4") (pintype "input"))
      (node (ref "SW2") (pin "16") (pinfunction "16_16") (pintype "passive"))
    )
    (net (code "95") (name "Net-(IC2A-D1)") (class "Default")
      (node (ref "IC2") (pin "3") (pinfunction "D1_3") (pintype "input"))
      (node (ref "SW2") (pin "15") (pinfunction "15_15") (pintype "passive"))
    )
    (net (code "96") (name "Net-(IC2A-D2)") (class "Default")
      (node (ref "IC2") (pin "2") (pinfunction "D2_2") (pintype "input"))
      (node (ref "SW2") (pin "14") (pinfunction "14_14") (pintype "passive"))
    )
    (net (code "97") (name "Net-(IC2A-D3)") (class "Default")
      (node (ref "IC2") (pin "1") (pinfunction "D3_1") (pintype "input"))
      (node (ref "SW2") (pin "13") (pinfunction "13_13") (pintype "passive"))
    )
    (net (code "98") (name "Net-(IC2A-D4)") (class "Default")
      (node (ref "IC2") (pin "15") (pinfunction "D4_15") (pintype "input"))
      (node (ref "SW2") (pin "12") (pinfunction "12_12") (pintype "passive"))
    )
    (net (code "99") (name "Net-(IC2A-D5)") (class "Default")
      (node (ref "IC2") (pin "14") (pinfunction "D5_14") (pintype "input"))
      (node (ref "SW2") (pin "11") (pinfunction "11_11") (pintype "passive"))
    )
    (net (code "100") (name "Net-(IC2A-D6)") (class "Default")
      (node (ref "IC2") (pin "13") (pinfunction "D6_13") (pintype "input"))
      (node (ref "SW2") (pin "10") (pinfunction "10_10") (pintype "passive"))
    )
    (net (code "101") (name "Net-(IC2A-D7)") (class "Default")
      (node (ref "IC2") (pin "12") (pinfunction "D7_12") (pintype "input"))
      (node (ref "SW2") (pin "9") (pinfunction "9_9") (pintype "passive"))
    )
    (net (code "102") (name "Net-(IC2A-Y)") (class "Default")
      (node (ref "IC2") (pin "5") (pinfunction "Y_5") (pintype "output"))
      (node (ref "IC5") (pin "2") (pinfunction "I1_2") (pintype "input"))
    )
    (net (code "103") (name "Net-(IC3A-D0)") (class "Default")
      (node (ref "IC3") (pin "4") (pinfunction "D0_4") (pintype "input"))
      (node (ref "SW3") (pin "16") (pinfunction "16_16") (pintype "passive"))
    )
    (net (code "104") (name "Net-(IC3A-D1)") (class "Default")
      (node (ref "IC3") (pin "3") (pinfunction "D1_3") (pintype "input"))
      (node (ref "SW3") (pin "15") (pinfunction "15_15") (pintype "passive"))
    )
    (net (code "105") (name "Net-(IC3A-D2)") (class "Default")
      (node (ref "IC3") (pin "2") (pinfunction "D2_2") (pintype "input"))
      (node (ref "SW3") (pin "14") (pinfunction "14_14") (pintype "passive"))
    )
    (net (code "106") (name "Net-(IC3A-D3)") (class "Default")
      (node (ref "IC3") (pin "1") (pinfunction "D3_1") (pintype "input"))
      (node (ref "SW3") (pin "13") (pinfunction "13_13") (pintype "passive"))
    )
    (net (code "107") (name "Net-(IC3A-D4)") (class "Default")
      (node (ref "IC3") (pin "15") (pinfunction "D4_15") (pintype "input"))
      (node (ref "SW3") (pin "12") (pinfunction "12_12") (pintype "passive"))
    )
    (net (code "108") (name "Net-(IC3A-D5)") (class "Default")
      (node (ref "IC3") (pin "14") (pinfunction "D5_14") (pintype "input"))
      (node (ref "SW3") (pin "11") (pinfunction "11_11") (pintype "passive"))
    )
    (net (code "109") (name "Net-(IC3A-D6)") (class "Default")
      (node (ref "IC3") (pin "13") (pinfunction "D6_13") (pintype "input"))
      (node (ref "SW3") (pin "10") (pinfunction "10_10") (pintype "passive"))
    )
    (net (code "110") (name "Net-(IC3A-D7)") (class "Default")
      (node (ref "IC3") (pin "12") (pinfunction "D7_12") (pintype "input"))
      (node (ref "SW3") (pin "9") (pinfunction "9_9") (pintype "passive"))
    )
    (net (code "111") (name "Net-(IC3A-Y)") (class "Default")
      (node (ref "IC3") (pin "5") (pinfunction "Y_5") (pintype "output"))
      (node (ref "IC5") (pin "4") (pinfunction "I2_4") (pintype "input"))
    )
    (net (code "112") (name "Net-(IC4A-D0)") (class "Default")
      (node (ref "IC4") (pin "4") (pinfunction "D0_4") (pintype "input"))
      (node (ref "SW4") (pin "16") (pinfunction "16_16") (pintype "passive"))
    )
    (net (code "113") (name "Net-(IC4A-D1)") (class "Default")
      (node (ref "IC4") (pin "3") (pinfunction "D1_3") (pintype "input"))
      (node (ref "SW4") (pin "15") (pinfunction "15_15") (pintype "passive"))
    )
    (net (code "114") (name "Net-(IC4A-D2)") (class "Default")
      (node (ref "IC4") (pin "2") (pinfunction "D2_2") (pintype "input"))
      (node (ref "SW4") (pin "14") (pinfunction "14_14") (pintype "passive"))
    )
    (net (code "115") (name "Net-(IC4A-D3)") (class "Default")
      (node (ref "IC4") (pin "1") (pinfunction "D3_1") (pintype "input"))
      (node (ref "SW4") (pin "13") (pinfunction "13_13") (pintype "passive"))
    )
    (net (code "116") (name "Net-(IC4A-D4)") (class "Default")
      (node (ref "IC4") (pin "15") (pinfunction "D4_15") (pintype "input"))
      (node (ref "SW4") (pin "12") (pinfunction "12_12") (pintype "passive"))
    )
    (net (code "117") (name "Net-(IC4A-D5)") (class "Default")
      (node (ref "IC4") (pin "14") (pinfunction "D5_14") (pintype "input"))
      (node (ref "SW4") (pin "11") (pinfunction "11_11") (pintype "passive"))
    )
    (net (code "118") (name "Net-(IC4A-D6)") (class "Default")
      (node (ref "IC4") (pin "13") (pinfunction "D6_13") (pintype "input"))
      (node (ref "SW4") (pin "10") (pinfunction "10_10") (pintype "passive"))
    )
    (net (code "119") (name "Net-(IC4A-D7)") (class "Default")
      (node (ref "IC4") (pin "12") (pinfunction "D7_12") (pintype "input"))
      (node (ref "SW4") (pin "9") (pinfunction "9_9") (pintype "passive"))
    )
    (net (code "120") (name "Net-(IC4A-Y)") (class "Default")
      (node (ref "IC4") (pin "5") (pinfunction "Y_5") (pintype "output"))
      (node (ref "IC5") (pin "5") (pinfunction "I3_5") (pintype "input"))
    )
    (net (code "121") (name "Net-(IC8-CV)") (class "Default")
      (node (ref "C48") (pin "2") (pinfunction "2_2") (pintype "passive"))
      (node (ref "IC8") (pin "5") (pinfunction "CV_5") (pintype "input"))
    )
    (net (code "122") (name "Net-(IC8-DIS)") (class "Default")
      (node (ref "IC8") (pin "7") (pinfunction "DIS_7") (pintype "input"))
      (node (ref "RA") (pin "2") (pinfunction "2_2") (pintype "passive"))
      (node (ref "RB") (pin "1") (pinfunction "1_1") (pintype "passive"))
    )
    (net (code "123") (name "Net-(IC8-THR)") (class "Default")
      (node (ref "C47") (pin "1") (pinfunction "1_1") (pintype "passive"))
      (node (ref "IC8") (pin "2") (pinfunction "TR_2") (pintype "input"))
      (node (ref "IC8") (pin "6") (pinfunction "THR_6") (pintype "input"))
      (node (ref "RB") (pin "2") (pinfunction "2_2") (pintype "passive"))
    )
    (net (code "124") (name "Net-(IC10B-CLK)") (class "Default")
      (node (ref "IC10") (pin "11") (pinfunction "CLK_11") (pintype "input"))
      (node (ref "IC18") (pin "6") (pinfunction "O_6") (pintype "output"))
    )
    (net (code "125") (name "Net-(IC10B-~{Q})") (class "Default")
      (node (ref "IC10") (pin "8") (pinfunction "~{Q}_8") (pintype "output"))
      (node (ref "IC11") (pin "11") (pinfunction "CLK_11") (pintype "input"))
    )
    (net (code "126") (name "Net-(IC12D-I)") (class "Default")
      (node (ref "IC12") (pin "9") (pinfunction "I_9") (pintype "input"))
      (node (ref "IC8") (pin "3") (pinfunction "Q_3") (pintype "output"))
      (node (ref "RL") (pin "2") (pinfunction "2_2") (pintype "passive"))
    )
    (net (code "127") (name "Net-(IC13A-A)") (class "Default")
      (node (ref "IC13") (pin "8") (pinfunction "A_8") (pintype "input"))
      (node (ref "IC14") (pin "8") (pinfunction "A_8") (pintype "input"))
      (node (ref "IC15") (pin "6") (pinfunction "ODD_6") (pintype "output"))
    )
    (net (code "128") (name "Net-(IC16B-Y1)") (class "Default")
      (node (ref "IC16") (pin "11") (pinfunction "Y1_11") (pintype "output"))
      (node (ref "IC22") (pin "1") (pinfunction "I_1") (pintype "input"))
    )
    (net (code "129") (name "Net-(IC17A-Y0)") (class "Default")
      (node (ref "IC17") (pin "4") (pinfunction "Y0_4") (pintype "output"))
      (node (ref "IC22") (pin "11") (pinfunction "I_11") (pintype "input"))
    )
    (net (code "130") (name "Net-(IC19A-I)") (class "Default")
      (node (ref "IC19") (pin "1") (pinfunction "I_1") (pintype "input"))
      (node (ref "IC7") (pin "5") (pinfunction "Y1_5") (pintype "output"))
    )
    (net (code "131") (name "Net-(IC19E-I)") (class "Default")
      (node (ref "IC19") (pin "11") (pinfunction "I_11") (pintype "input"))
      (node (ref "IC7") (pin "12") (pinfunction "Y0_12") (pintype "output"))
    )
    (net (code "132") (name "Net-(IC21A-Y0)") (class "Default")
      (node (ref "IC21") (pin "4") (pinfunction "Y0_4") (pintype "output"))
      (node (ref "SW1") (pin "1") (pinfunction "1_1") (pintype "passive"))
      (node (ref "SW1") (pin "2") (pinfunction "2_2") (pintype "passive"))
      (node (ref "SW1") (pin "3") (pinfunction "3_3") (pintype "passive"))
      (node (ref "SW1") (pin "4") (pinfunction "4_4") (pintype "passive"))
      (node (ref "SW1") (pin "5") (pinfunction "5_5") (pintype "passive"))
      (node (ref "SW1") (pin "6") (pinfunction "6_6") (pintype "passive"))
      (node (ref "SW1") (pin "7") (pinfunction "7_7") (pintype "passive"))
      (node (ref "SW1") (pin "8") (pinfunction "8_8") (pintype "passive"))
    )
    (net (code "133") (name "Net-(IC21A-Y1)") (class "Default")
      (node (ref "IC21") (pin "5") (pinfunction "Y1_5") (pintype "output"))
      (node (ref "SW2") (pin "1") (pinfunction "1_1") (pintype "passive"))
      (node (ref "SW2") (pin "2") (pinfunction "2_2") (pintype "passive"))
      (node (ref "SW2") (pin "3") (pinfunction "3_3") (pintype "passive"))
      (node (ref "SW2") (pin "4") (pinfunction "4_4") (pintype "passive"))
      (node (ref "SW2") (pin "5") (pinfunction "5_5") (pintype "passive"))
      (node (ref "SW2") (pin "6") (pinfunction "6_6") (pintype "passive"))
      (node (ref "SW2") (pin "7") (pinfunction "7_7") (pintype "passive"))
      (node (ref "SW2") (pin "8") (pinfunction "8_8") (pintype "passive"))
    )
    (net (code "134") (name "Net-(IC21A-Y2)") (class "Default")
      (node (ref "IC21") (pin "6") (pinfunction "Y2_6") (pintype "output"))
      (node (ref "SW3") (pin "1") (pinfunction "1_1") (pintype "passive"))
      (node (ref "SW3") (pin "2") (pinfunction "2_2") (pintype "passive"))
      (node (ref "SW3") (pin "3") (pinfunction "3_3") (pintype "passive"))
      (node (ref "SW3") (pin "4") (pinfunction "4_4") (pintype "passive"))
      (node (ref "SW3") (pin "5") (pinfunction "5_5") (pintype "passive"))
      (node (ref "SW3") (pin "6") (pinfunction "6_6") (pintype "passive"))
      (node (ref "SW3") (pin "7") (pinfunction "7_7") (pintype "passive"))
      (node (ref "SW3") (pin "8") (pinfunction "8_8") (pintype "passive"))
    )
    (net (code "135") (name "Net-(IC21A-Y3)") (class "Default")
      (node (ref "IC21") (pin "7") (pinfunction "Y3_7") (pintype "output"))
      (node (ref "SW4") (pin "1") (pinfunction "1_1") (pintype "passive"))
      (node (ref "SW4") (pin "2") (pinfunction "2_2") (pintype "passive"))
      (node (ref "SW4") (pin "3") (pinfunction "3_3") (pintype "passive"))
      (node (ref "SW4") (pin "4") (pinfunction "4_4") (pintype "passive"))
      (node (ref "SW4") (pin "5") (pinfunction "5_5") (pintype "passive"))
      (node (ref "SW4") (pin "6") (pinfunction "6_6") (pintype "passive"))
      (node (ref "SW4") (pin "7") (pinfunction "7_7") (pintype "passive"))
      (node (ref "SW4") (pin "8") (pinfunction "8_8") (pintype "passive"))
    )
    (net (code "136") (name "Net-(IC36A-Y0)") (class "Default")
      (node (ref "IC36") (pin "15") (pinfunction "Y0_15") (pintype "output"))
      (node (ref "PAD2") (pin "1") (pinfunction "P_1") (pintype "passive"))
    )
    (net (code "137") (name "Net-(IC36A-Y1)") (class "Default")
      (node (ref "IC36") (pin "14") (pinfunction "Y1_14") (pintype "output"))
      (node (ref "PAD3") (pin "1") (pinfunction "P_1") (pintype "passive"))
    )
    (net (code "138") (name "Net-(IC36A-Y2)") (class "Default")
      (node (ref "IC36") (pin "13") (pinfunction "Y2_13") (pintype "output"))
      (node (ref "PAD4") (pin "1") (pinfunction "P_1") (pintype "passive"))
    )
    (net (code "139") (name "Net-(IC36A-Y3)") (class "Default")
      (node (ref "IC36") (pin "12") (pinfunction "Y3_12") (pintype "output"))
      (node (ref "PAD5") (pin "1") (pinfunction "P_1") (pintype "passive"))
    )
    (net (code "140") (name "Net-(IC36A-Y4)") (class "Default")
      (node (ref "IC36") (pin "11") (pinfunction "Y4_11") (pintype "output"))
      (node (ref "PAD6") (pin "1") (pinfunction "P_1") (pintype "passive"))
    )
    (net (code "141") (name "Net-(IC36A-Y5)") (class "Default")
      (node (ref "IC36") (pin "10") (pinfunction "Y5_10") (pintype "output"))
      (node (ref "PAD7") (pin "1") (pinfunction "P_1") (pintype "passive"))
    )
    (net (code "142") (name "Net-(IC36A-Y6)") (class "Default")
      (node (ref "IC36") (pin "9") (pinfunction "Y6_9") (pintype "output"))
      (node (ref "PAD8") (pin "1") (pinfunction "P_1") (pintype "passive"))
    )
    (net (code "143") (name "Net-(IC36A-Y7)") (class "Default")
      (node (ref "IC36") (pin "7") (pinfunction "Y7_7") (pintype "output"))
      (node (ref "PAD9") (pin "1") (pinfunction "P_1") (pintype "passive"))
    )
    (net (code "144") (name "PBIT") (class "Default")
      (node (ref "IC14") (pin "6") (pinfunction "ODD_6") (pintype "output"))
      (node (ref "IC35") (pin "11") (pinfunction "A1_11") (pintype "input"))
    )
    (net (code "145") (name "PCA") (class "Default")
      (node (ref "IC12") (pin "8") (pinfunction "O_8") (pintype "output"))
      (node (ref "IC37") (pin "8") (pinfunction "A4_8") (pintype "input"))
      (node (ref "IC55") (pin "5") (pinfunction "I1_5") (pintype "input"))
    )
    (net (code "146") (name "PER") (class "Default")
      (node (ref "IC30") (pin "2") (pinfunction "A1_2") (pintype "input"))
      (node (ref "IC9") (pin "9") (pinfunction "Q_9") (pintype "output"))
      (node (ref "SV1") (pin "21") (pinfunction "21_21") (pintype "passive"))
    )
    (net (code "147") (name "PIE") (class "Default")
      (node (ref "IC30") (pin "17") (pinfunction "A4_17") (pintype "input"))
      (node (ref "IC55") (pin "4") (pinfunction "I0_4") (pintype "input"))
      (node (ref "INTENB") (pin "2") (pinfunction "QB_2") (pintype "output"))
      (node (ref "SV1") (pin "5") (pinfunction "5_5") (pintype "passive"))
    )
    (net (code "148") (name "PROTECT") (class "Default")
      (node (ref "IC5") (pin "6") (pinfunction "O_6") (pintype "output"))
      (node (ref "IC6") (pin "3") (pinfunction "B_3") (pintype "input"))
    )
    (net (code "149") (name "START") (class "Default")
      (node (ref "IC12") (pin "5") (pinfunction "I_5") (pintype "input"))
      (node (ref "IC18") (pin "3") (pinfunction "O_3") (pintype "output"))
    )
    (net (code "150") (name "VCC") (class "Default")
      (node (ref "C1") (pin "1") (pinfunction "1_1") (pintype "passive"))
      (node (ref "C10") (pin "1") (pinfunction "1_1") (pintype "passive"))
      (node (ref "C11") (pin "1") (pinfunction "1_1") (pintype "passive"))
      (node (ref "C12") (pin "1") (pinfunction "1_1") (pintype "passive"))
      (node (ref "C13") (pin "1") (pinfunction "1_1") (pintype "passive"))
      (node (ref "C14") (pin "1") (pinfunction "1_1") (pintype "passive"))
      (node (ref "C15") (pin "1") (pinfunction "1_1") (pintype "passive"))
      (node (ref "C16") (pin "1") (pinfunction "1_1") (pintype "passive"))
      (node (ref "C17") (pin "1") (pinfunction "1_1") (pintype "passive"))
      (node (ref "C18") (pin "1") (pinfunction "1_1") (pintype "passive"))
      (node (ref "C19") (pin "1") (pinfunction "1_1") (pintype "passive"))
      (node (ref "C2") (pin "1") (pinfunction "1_1") (pintype "passive"))
      (node (ref "C20") (pin "1") (pinfunction "1_1") (pintype "passive"))
      (node (ref "C21") (pin "1") (pinfunction "1_1") (pintype "passive"))
      (node (ref "C22") (pin "1") (pinfunction "1_1") (pintype "passive"))
      (node (ref "C23") (pin "1") (pinfunction "1_1") (pintype "passive"))
      (node (ref "C24") (pin "1") (pinfunction "1_1") (pintype "passive"))
      (node (ref "C25") (pin "1") (pinfunction "1_1") (pintype "passive"))
      (node (ref "C26") (pin "1") (pinfunction "1_1") (pintype "passive"))
      (node (ref "C27") (pin "1") (pinfunction "1_1") (pintype "passive"))
      (node (ref "C28") (pin "1") (pinfunction "1_1") (pintype "passive"))
      (node (ref "C29") (pin "1") (pinfunction "1_1") (pintype "passive"))
      (node (ref "C3") (pin "1") (pinfunction "1_1") (pintype "passive"))
      (node (ref "C30") (pin "1") (pinfunction "1_1") (pintype "passive"))
      (node (ref "C31") (pin "1") (pinfunction "1_1") (pintype "passive"))
      (node (ref "C32") (pin "1") (pinfunction "1_1") (pintype "passive"))
      (node (ref "C33") (pin "1") (pinfunction "1_1") (pintype "passive"))
      (node (ref "C34") (pin "1") (pinfunction "1_1") (pintype "passive"))
      (node (ref "C35") (pin "1") (pinfunction "1_1") (pintype "passive"))
      (node (ref "C36") (pin "1") (pinfunction "1_1") (pintype "passive"))
      (node (ref "C37") (pin "1") (pinfunction "1_1") (pintype "passive"))
      (node (ref "C38") (pin "1") (pinfunction "1_1") (pintype "passive"))
      (node (ref "C39") (pin "1") (pinfunction "1_1") (pintype "passive"))
      (node (ref "C4") (pin "1") (pinfunction "1_1") (pintype "passive"))
      (node (ref "C40") (pin "1") (pinfunction "1_1") (pintype "passive"))
      (node (ref "C41") (pin "1") (pinfunction "1_1") (pintype "passive"))
      (node (ref "C42") (pin "1") (pinfunction "1_1") (pintype "passive"))
      (node (ref "C43") (pin "1") (pinfunction "1_1") (pintype "passive"))
      (node (ref "C44") (pin "1") (pinfunction "1_1") (pintype "passive"))
      (node (ref "C45") (pin "+") (pinfunction "+_+") (pintype "passive"))
      (node (ref "C46") (pin "1") (pinfunction "1_1") (pintype "passive"))
      (node (ref "C48") (pin "1") (pinfunction "1_1") (pintype "passive"))
      (node (ref "C5") (pin "1") (pinfunction "1_1") (pintype "passive"))
      (node (ref "C6") (pin "1") (pinfunction "1_1") (pintype "passive"))
      (node (ref "C7") (pin "1") (pinfunction "1_1") (pintype "passive"))
      (node (ref "C8") (pin "1") (pinfunction "1_1") (pintype "passive"))
      (node (ref "C9") (pin "1") (pinfunction "1_1") (pintype "passive"))
      (node (ref "IC11") (pin "10") (pinfunction "PRE_10") (pintype "input"))
      (node (ref "IC11") (pin "12") (pinfunction "D_12") (pintype "input"))
      (node (ref "IC11") (pin "4") (pinfunction "PRE_4") (pintype "input"))
      (node (ref "IC14") (pin "3") (pinfunction "EI_3") (pintype "input"))
      (node (ref "IC15") (pin "3") (pinfunction "EI_3") (pintype "input"))
      (node (ref "IC36") (pin "6") (pinfunction "G1_6") (pintype "input"))
      (node (ref "IC8") (pin "4") (pinfunction "R_4") (pintype "input"))
      (node (ref "IC8") (pin "8") (pinfunction "V+_8") (pintype "power_in"))
      (node (ref "J3") (pin "2") (pinfunction "2_2") (pintype "passive"))
      (node (ref "J4") (pin "2") (pinfunction "2_2") (pintype "passive"))
      (node (ref "J5") (pin "2") (pinfunction "2_2") (pintype "passive"))
      (node (ref "J7") (pin "2") (pinfunction "2_2") (pintype "passive"))
      (node (ref "R1") (pin "2") (pinfunction "2_2") (pintype "passive"))
      (node (ref "R2") (pin "2") (pinfunction "2_2") (pintype "passive"))
      (node (ref "RA") (pin "1") (pinfunction "1_1") (pintype "passive"))
      (node (ref "RL") (pin "1") (pinfunction "1_1") (pintype "passive"))
      (node (ref "RS08") (pin "2") (pinfunction "2_2") (pintype "passive"))
      (node (ref "SV1") (pin "25") (pinfunction "25_25") (pintype "passive"))
      (node (ref "SV1") (pin "26") (pinfunction "26_26") (pintype "passive"))
    )
    (net (code "151") (name "WLS") (class "Default")
      (node (ref "IC37") (pin "4") (pinfunction "A2_4") (pintype "input"))
      (node (ref "IC9") (pin "5") (pinfunction "Q_5") (pintype "output"))
      (node (ref "SV1") (pin "15") (pinfunction "15_15") (pintype "passive"))
    )
    (net (code "152") (name "WRITING") (class "Default")
      (node (ref "IC10") (pin "5") (pinfunction "Q_5") (pintype "output"))
      (node (ref "IC41") (pin "13") (pinfunction "B_13") (pintype "input"))
      (node (ref "IC41") (pin "14") (pinfunction "A_14") (pintype "input"))
      (node (ref "IC6") (pin "2") (pinfunction "A_2") (pintype "input"))
      (node (ref "RS08") (pin "18") (pinfunction "18_18") (pintype "passive"))
      (node (ref "SV1") (pin "9") (pinfunction "9_9") (pintype "passive"))
    )
    (net (code "153") (name "unconnected-(C35L-Pad20)") (class "Default")
      (node (ref "C35L") (pin "20") (pinfunction "20_20") (pintype "passive"))
    )
    (net (code "154") (name "unconnected-(C35L-Pad40)") (class "Default")
      (node (ref "C35L") (pin "40") (pinfunction "40_40") (pintype "passive"))
    )
    (net (code "155") (name "unconnected-(C36L-Pad20)") (class "Default")
      (node (ref "C36L") (pin "20") (pinfunction "20_20") (pintype "passive"))
    )
    (net (code "156") (name "unconnected-(C36L-Pad40)") (class "Default")
      (node (ref "C36L") (pin "40") (pinfunction "40_40") (pintype "passive"))
    )
    (net (code "157") (name "unconnected-(D34L-Pad20)") (class "Default")
      (node (ref "D34L") (pin "20") (pinfunction "20_20") (pintype "passive"))
    )
    (net (code "158") (name "unconnected-(D34L-Pad36)") (class "Default")
      (node (ref "D34L") (pin "36") (pinfunction "36_36") (pintype "passive"))
    )
    (net (code "159") (name "unconnected-(D34L-Pad38)") (class "Default")
      (node (ref "D34L") (pin "38") (pinfunction "38_38") (pintype "passive"))
    )
    (net (code "160") (name "unconnected-(D34L-Pad40)") (class "Default")
      (node (ref "D34L") (pin "40") (pinfunction "40_40") (pintype "passive"))
    )
    (net (code "161") (name "unconnected-(D35L-Pad20)") (class "Default")
      (node (ref "D35L") (pin "20") (pinfunction "20_20") (pintype "passive"))
    )
    (net (code "162") (name "unconnected-(D35L-Pad40)") (class "Default")
      (node (ref "D35L") (pin "40") (pinfunction "40_40") (pintype "passive"))
    )
    (net (code "163") (name "unconnected-(D36L-Pad20)") (class "Default")
      (node (ref "D36L") (pin "20") (pinfunction "20_20") (pintype "passive"))
    )
    (net (code "164") (name "unconnected-(D36L-Pad40)") (class "Default")
      (node (ref "D36L") (pin "40") (pinfunction "40_40") (pintype "passive"))
    )
    (net (code "165") (name "unconnected-(DAR4-7A-BO-Pad13)") (class "Default")
      (node (ref "DAR4-7") (pin "13") (pinfunction "BO_13") (pintype "output"))
    )
    (net (code "166") (name "unconnected-(DAR4-7A-CO-Pad12)") (class "Default")
      (node (ref "DAR4-7") (pin "12") (pinfunction "CO_12") (pintype "output"))
    )
    (net (code "167") (name "unconnected-(DAR8-11A-BO-Pad13)") (class "Default")
      (node (ref "DAR8-11") (pin "13") (pinfunction "BO_13") (pintype "output"))
    )
    (net (code "168") (name "unconnected-(DMA0-3A-BO-Pad13)") (class "Default")
      (node (ref "DMA0-3") (pin "13") (pinfunction "BO_13") (pintype "output"))
    )
    (net (code "169") (name "unconnected-(DMA4-7A-BO-Pad13)") (class "Default")
      (node (ref "DMA4-7") (pin "13") (pinfunction "BO_13") (pintype "output"))
    )
    (net (code "170") (name "unconnected-(DMA8-11A-BO-Pad13)") (class "Default")
      (node (ref "DMA8-11") (pin "13") (pinfunction "BO_13") (pintype "output"))
    )
    (net (code "171") (name "unconnected-(FIELDA-BO-Pad13)") (class "Default")
      (node (ref "FIELD") (pin "13") (pinfunction "BO_13") (pintype "output"))
    )
    (net (code "172") (name "unconnected-(FIELDA-CO-Pad12)") (class "Default")
      (node (ref "FIELD") (pin "12") (pinfunction "CO_12") (pintype "output"))
    )
    (net (code "173") (name "unconnected-(FIELDA-QD-Pad7)") (class "Default")
      (node (ref "FIELD") (pin "7") (pinfunction "QD_7") (pintype "output"))
    )
    (net (code "174") (name "unconnected-(IC1A-W-Pad6)") (class "Default")
      (node (ref "IC1") (pin "6") (pinfunction "W_6") (pintype "output"))
    )
    (net (code "175") (name "unconnected-(IC2A-W-Pad6)") (class "Default")
      (node (ref "IC2") (pin "6") (pinfunction "W_6") (pintype "output"))
    )
    (net (code "176") (name "unconnected-(IC3A-W-Pad6)") (class "Default")
      (node (ref "IC3") (pin "6") (pinfunction "W_6") (pintype "output"))
    )
    (net (code "177") (name "unconnected-(IC4A-W-Pad6)") (class "Default")
      (node (ref "IC4") (pin "6") (pinfunction "W_6") (pintype "output"))
    )
    (net (code "178") (name "unconnected-(IC6A-Y0-Pad4)") (class "Default")
      (node (ref "IC6") (pin "4") (pinfunction "Y0_4") (pintype "output"))
    )
    (net (code "179") (name "unconnected-(IC6A-Y2-Pad6)") (class "Default")
      (node (ref "IC6") (pin "6") (pinfunction "Y2_6") (pintype "output"))
    )
    (net (code "180") (name "unconnected-(IC6B-Y2-Pad10)") (class "Default")
      (node (ref "IC6") (pin "10") (pinfunction "Y2_10") (pintype "output"))
    )
    (net (code "181") (name "unconnected-(IC6B-Y3-Pad9)") (class "Default")
      (node (ref "IC6") (pin "9") (pinfunction "Y3_9") (pintype "output"))
    )
    (net (code "182") (name "unconnected-(IC7A-Y0-Pad4)") (class "Default")
      (node (ref "IC7") (pin "4") (pinfunction "Y0_4") (pintype "output"))
    )
    (net (code "183") (name "unconnected-(IC7A-Y2-Pad6)") (class "Default")
      (node (ref "IC7") (pin "6") (pinfunction "Y2_6") (pintype "output"))
    )
    (net (code "184") (name "unconnected-(IC7A-Y3-Pad7)") (class "Default")
      (node (ref "IC7") (pin "7") (pinfunction "Y3_7") (pintype "output"))
    )
    (net (code "185") (name "unconnected-(IC7B-Y1-Pad11)") (class "Default")
      (node (ref "IC7") (pin "11") (pinfunction "Y1_11") (pintype "output"))
    )
    (net (code "186") (name "unconnected-(IC7B-Y2-Pad10)") (class "Default")
      (node (ref "IC7") (pin "10") (pinfunction "Y2_10") (pintype "output"))
    )
    (net (code "187") (name "unconnected-(IC7B-Y3-Pad9)") (class "Default")
      (node (ref "IC7") (pin "9") (pinfunction "Y3_9") (pintype "output"))
    )
    (net (code "188") (name "unconnected-(IC10A-~{Q}-Pad6)") (class "Default")
      (node (ref "IC10") (pin "6") (pinfunction "~{Q}_6") (pintype "output"))
    )
    (net (code "189") (name "unconnected-(IC11A-Q-Pad5)") (class "Default")
      (node (ref "IC11") (pin "5") (pinfunction "Q_5") (pintype "output"))
    )
    (net (code "190") (name "unconnected-(IC11B-~{Q}-Pad8)") (class "Default")
      (node (ref "IC11") (pin "8") (pinfunction "~{Q}_8") (pintype "output"))
    )
    (net (code "191") (name "unconnected-(IC13A-ODD-Pad6)") (class "Default")
      (node (ref "IC13") (pin "6") (pinfunction "ODD_6") (pintype "output"))
    )
    (net (code "192") (name "unconnected-(IC14A-EVN-Pad5)") (class "Default")
      (node (ref "IC14") (pin "5") (pinfunction "EVN_5") (pintype "output"))
    )
    (net (code "193") (name "unconnected-(IC15A-EVN-Pad5)") (class "Default")
      (node (ref "IC15") (pin "5") (pinfunction "EVN_5") (pintype "output"))
    )
    (net (code "194") (name "unconnected-(IC16A-Y1-Pad5)") (class "Default")
      (node (ref "IC16") (pin "5") (pinfunction "Y1_5") (pintype "output"))
    )
    (net (code "195") (name "unconnected-(IC16A-Y2-Pad6)") (class "Default")
      (node (ref "IC16") (pin "6") (pinfunction "Y2_6") (pintype "output"))
    )
    (net (code "196") (name "unconnected-(IC16A-Y3-Pad7)") (class "Default")
      (node (ref "IC16") (pin "7") (pinfunction "Y3_7") (pintype "output"))
    )
    (net (code "197") (name "unconnected-(IC16B-Y2-Pad10)") (class "Default")
      (node (ref "IC16") (pin "10") (pinfunction "Y2_10") (pintype "output"))
    )
    (net (code "198") (name "unconnected-(IC16B-Y3-Pad9)") (class "Default")
      (node (ref "IC16") (pin "9") (pinfunction "Y3_9") (pintype "output"))
    )
    (net (code "199") (name "unconnected-(IC17A-Y1-Pad5)") (class "Default")
      (node (ref "IC17") (pin "5") (pinfunction "Y1_5") (pintype "output"))
    )
    (net (code "200") (name "unconnected-(IC17A-Y2-Pad6)") (class "Default")
      (node (ref "IC17") (pin "6") (pinfunction "Y2_6") (pintype "output"))
    )
    (net (code "201") (name "unconnected-(IC17A-Y3-Pad7)") (class "Default")
      (node (ref "IC17") (pin "7") (pinfunction "Y3_7") (pintype "output"))
    )
    (net (code "202") (name "unconnected-(IC20-Pad1)") (class "Default")
      (node (ref "IC20") (pin "1") (pinfunction "1_1") (pintype "passive"))
    )
    (net (code "203") (name "unconnected-(IC20-Pad2)") (class "Default")
      (node (ref "IC20") (pin "2") (pinfunction "2_2") (pintype "passive"))
    )
    (net (code "204") (name "unconnected-(IC20-Pad3)") (class "Default")
      (node (ref "IC20") (pin "3") (pinfunction "3_3") (pintype "passive"))
    )
    (net (code "205") (name "unconnected-(IC20-Pad4)") (class "Default")
      (node (ref "IC20") (pin "4") (pinfunction "4_4") (pintype "passive"))
    )
    (net (code "206") (name "unconnected-(IC20-Pad5)") (class "Default")
      (node (ref "IC20") (pin "5") (pinfunction "5_5") (pintype "passive"))
    )
    (net (code "207") (name "unconnected-(IC20-Pad6)") (class "Default")
      (node (ref "IC20") (pin "6") (pinfunction "6_6") (pintype "passive"))
    )
    (net (code "208") (name "unconnected-(IC20-Pad7)") (class "Default")
      (node (ref "IC20") (pin "7") (pinfunction "7_7") (pintype "passive"))
    )
    (net (code "209") (name "unconnected-(IC20-Pad8)") (class "Default")
      (node (ref "IC20") (pin "8") (pinfunction "8_8") (pintype "passive"))
    )
    (net (code "210") (name "unconnected-(IC20-Pad9)") (class "Default")
      (node (ref "IC20") (pin "9") (pinfunction "9_9") (pintype "passive"))
    )
    (net (code "211") (name "unconnected-(IC20-Pad10)") (class "Default")
      (node (ref "IC20") (pin "10") (pinfunction "10_10") (pintype "passive"))
    )
    (net (code "212") (name "unconnected-(IC20-Pad11)") (class "Default")
      (node (ref "IC20") (pin "11") (pinfunction "11_11") (pintype "passive"))
    )
    (net (code "213") (name "unconnected-(IC20-Pad12)") (class "Default")
      (node (ref "IC20") (pin "12") (pinfunction "12_12") (pintype "passive"))
    )
    (net (code "214") (name "unconnected-(IC20-Pad13)") (class "Default")
      (node (ref "IC20") (pin "13") (pinfunction "13_13") (pintype "passive"))
    )
    (net (code "215") (name "unconnected-(IC20-Pad14)") (class "Default")
      (node (ref "IC20") (pin "14") (pinfunction "14_14") (pintype "passive"))
    )
    (net (code "216") (name "unconnected-(IC20-Pad15)") (class "Default")
      (node (ref "IC20") (pin "15") (pinfunction "15_15") (pintype "passive"))
    )
    (net (code "217") (name "unconnected-(IC20-Pad16)") (class "Default")
      (node (ref "IC20") (pin "16") (pinfunction "16_16") (pintype "passive"))
    )
    (net (code "218") (name "unconnected-(IC20-Pad17)") (class "Default")
      (node (ref "IC20") (pin "17") (pinfunction "17_17") (pintype "passive"))
    )
    (net (code "219") (name "unconnected-(IC20-Pad18)") (class "Default")
      (node (ref "IC20") (pin "18") (pinfunction "18_18") (pintype "passive"))
    )
    (net (code "220") (name "unconnected-(IC20-Pad19)") (class "Default")
      (node (ref "IC20") (pin "19") (pinfunction "19_19") (pintype "passive"))
    )
    (net (code "221") (name "unconnected-(IC20-Pad20)") (class "Default")
      (node (ref "IC20") (pin "20") (pinfunction "20_20") (pintype "passive"))
    )
    (net (code "222") (name "unconnected-(IC21B-Y0-Pad12)") (class "Default")
      (node (ref "IC21") (pin "12") (pinfunction "Y0_12") (pintype "output"))
    )
    (net (code "223") (name "unconnected-(IC21B-Y1-Pad11)") (class "Default")
      (node (ref "IC21") (pin "11") (pinfunction "Y1_11") (pintype "output"))
    )
    (net (code "224") (name "unconnected-(IC21B-Y2-Pad10)") (class "Default")
      (node (ref "IC21") (pin "10") (pinfunction "Y2_10") (pintype "output"))
    )
    (net (code "225") (name "unconnected-(IC25A-Y3-Pad12)") (class "Default")
      (node (ref "IC25") (pin "12") (pinfunction "Y3_12") (pintype "output"))
    )
    (net (code "226") (name "unconnected-(IC25A-Y5-Pad10)") (class "Default")
      (node (ref "IC25") (pin "10") (pinfunction "Y5_10") (pintype "output"))
    )
    (net (code "227") (name "unconnected-(IC25A-Y6-Pad9)") (class "Default")
      (node (ref "IC25") (pin "9") (pinfunction "Y6_9") (pintype "output"))
    )
    (net (code "228") (name "unconnected-(IC25A-Y7-Pad7)") (class "Default")
      (node (ref "IC25") (pin "7") (pinfunction "Y7_7") (pintype "output"))
    )
    (net (code "229") (name "unconnected-(IC26A-Y4-Pad12)") (class "Default")
      (node (ref "IC26") (pin "12") (pinfunction "Y4_12") (pintype "tri_state"))
    )
    (net (code "230") (name "unconnected-(IC29A-Y3-Pad12)") (class "Default")
      (node (ref "IC29") (pin "12") (pinfunction "Y3_12") (pintype "output"))
    )
    (net (code "231") (name "unconnected-(IC29A-Y5-Pad10)") (class "Default")
      (node (ref "IC29") (pin "10") (pinfunction "Y5_10") (pintype "output"))
    )
    (net (code "232") (name "unconnected-(IC29A-Y6-Pad9)") (class "Default")
      (node (ref "IC29") (pin "9") (pinfunction "Y6_9") (pintype "output"))
    )
    (net (code "233") (name "unconnected-(IC29A-Y7-Pad7)") (class "Default")
      (node (ref "IC29") (pin "7") (pinfunction "Y7_7") (pintype "output"))
    )
    (net (code "234") (name "unconnected-(IC32A-Y3-Pad12)") (class "Default")
      (node (ref "IC32") (pin "12") (pinfunction "Y3_12") (pintype "output"))
    )
    (net (code "235") (name "unconnected-(IC32A-Y5-Pad10)") (class "Default")
      (node (ref "IC32") (pin "10") (pinfunction "Y5_10") (pintype "output"))
    )
    (net (code "236") (name "unconnected-(IC32A-Y6-Pad9)") (class "Default")
      (node (ref "IC32") (pin "9") (pinfunction "Y6_9") (pintype "output"))
    )
    (net (code "237") (name "unconnected-(IC32A-Y7-Pad7)") (class "Default")
      (node (ref "IC32") (pin "7") (pinfunction "Y7_7") (pintype "output"))
    )
    (net (code "238") (name "unconnected-(IC35B-Y2-Pad7)") (class "Default")
      (node (ref "IC35") (pin "7") (pinfunction "Y2_7") (pintype "tri_state"))
    )
    (net (code "239") (name "unconnected-(IC35B-Y3-Pad5)") (class "Default")
      (node (ref "IC35") (pin "5") (pinfunction "Y3_5") (pintype "tri_state"))
    )
    (net (code "240") (name "unconnected-(IC35B-Y4-Pad3)") (class "Default")
      (node (ref "IC35") (pin "3") (pinfunction "Y4_3") (pintype "tri_state"))
    )
    (net (code "241") (name "unconnected-(IC41A-Y1-Pad5)") (class "Default")
      (node (ref "IC41") (pin "5") (pinfunction "Y1_5") (pintype "output"))
    )
    (net (code "242") (name "unconnected-(IC41A-Y2-Pad6)") (class "Default")
      (node (ref "IC41") (pin "6") (pinfunction "Y2_6") (pintype "output"))
    )
    (net (code "243") (name "unconnected-(IC41B-Y1-Pad11)") (class "Default")
      (node (ref "IC41") (pin "11") (pinfunction "Y1_11") (pintype "output"))
    )
    (net (code "244") (name "unconnected-(IC41B-Y2-Pad10)") (class "Default")
      (node (ref "IC41") (pin "10") (pinfunction "Y2_10") (pintype "output"))
    )
    (net (code "245") (name "unconnected-(INTENBA-BO-Pad13)") (class "Default")
      (node (ref "INTENB") (pin "13") (pinfunction "BO_13") (pintype "output"))
    )
    (net (code "246") (name "unconnected-(INTENBA-CO-Pad12)") (class "Default")
      (node (ref "INTENB") (pin "12") (pinfunction "CO_12") (pintype "output"))
    )
    (net (code "247") (name "unconnected-(INTENBA-QD-Pad7)") (class "Default")
      (node (ref "INTENB") (pin "7") (pinfunction "QD_7") (pintype "output"))
    )
    (net (code "248") (name "unconnected-(SV1-Pad7)") (class "Default")
      (node (ref "SV1") (pin "7") (pinfunction "7_7") (pintype "passive"))
    )
    (net (code "249") (name "unconnected-(SV1-Pad13)") (class "Default")
      (node (ref "SV1") (pin "13") (pinfunction "13_13") (pintype "passive"))
    )
    (net (code "250") (name "~{3CYC}") (class "Default")
      (node (ref "C35L") (pin "28") (pinfunction "28_28") (pintype "passive"))
      (node (ref "J2") (pin "1") (pinfunction "1_1") (pintype "passive"))
    )
    (net (code "251") (name "~{601}") (class "Default")
      (node (ref "IC11") (pin "13") (pinfunction "CLR_13") (pintype "input"))
      (node (ref "IC18") (pin "12") (pinfunction "I0_12") (pintype "input"))
      (node (ref "IC23") (pin "3") (pinfunction "CLK_3") (pintype "input"))
      (node (ref "IC32") (pin "15") (pinfunction "Y0_15") (pintype "output"))
      (node (ref "IC9") (pin "11") (pinfunction "CLK_11") (pintype "input"))
      (node (ref "IC9") (pin "3") (pinfunction "CLK_3") (pintype "input"))
    )
    (net (code "252") (name "~{602}") (class "Default")
      (node (ref "IC10") (pin "3") (pinfunction "CLK_3") (pintype "input"))
      (node (ref "IC18") (pin "1") (pinfunction "I0_1") (pintype "input"))
      (node (ref "IC29") (pin "15") (pinfunction "Y0_15") (pintype "output"))
    )
    (net (code "253") (name "~{604}") (class "Default")
      (node (ref "IC10") (pin "4") (pinfunction "PRE_4") (pintype "input"))
      (node (ref "IC18") (pin "2") (pinfunction "I1_2") (pintype "input"))
      (node (ref "IC25") (pin "15") (pinfunction "Y0_15") (pintype "output"))
    )
    (net (code "254") (name "~{611}") (class "Default")
      (node (ref "FIELD") (pin "14") (pinfunction "CLR_14") (pintype "input"))
      (node (ref "IC32") (pin "14") (pinfunction "Y1_14") (pintype "output"))
      (node (ref "INTENB") (pin "14") (pinfunction "CLR_14") (pintype "input"))
    )
    (net (code "255") (name "~{612}") (class "Default")
      (node (ref "IC19") (pin "5") (pinfunction "I_5") (pintype "input"))
      (node (ref "IC29") (pin "14") (pinfunction "Y1_14") (pintype "output"))
    )
    (net (code "256") (name "~{614}") (class "Default")
      (node (ref "IC22") (pin "3") (pinfunction "I_3") (pintype "input"))
      (node (ref "IC25") (pin "14") (pinfunction "Y1_14") (pintype "output"))
      (node (ref "IC6") (pin "13") (pinfunction "B_13") (pintype "input"))
    )
    (net (code "257") (name "~{621}") (class "Default")
      (node (ref "IC32") (pin "13") (pinfunction "Y2_13") (pintype "output"))
      (node (ref "IC7") (pin "3") (pinfunction "B_3") (pintype "input"))
    )
    (net (code "258") (name "~{622}") (class "Default")
      (node (ref "IC29") (pin "13") (pinfunction "Y2_13") (pintype "output"))
      (node (ref "IC7") (pin "13") (pinfunction "B_13") (pintype "input"))
    )
    (net (code "259") (name "~{624}") (class "Default")
      (node (ref "IC22") (pin "13") (pinfunction "I_13") (pintype "input"))
      (node (ref "IC24") (pin "1") (pinfunction "G_1") (pintype "input"))
      (node (ref "IC25") (pin "13") (pinfunction "Y2_13") (pintype "output"))
      (node (ref "IC31") (pin "1") (pinfunction "G_1") (pintype "input"))
      (node (ref "IC38") (pin "1") (pinfunction "G_1") (pintype "input"))
    )
    (net (code "260") (name "~{641}") (class "Default")
      (node (ref "IC16") (pin "13") (pinfunction "B_13") (pintype "input"))
      (node (ref "IC32") (pin "11") (pinfunction "Y4_11") (pintype "output"))
    )
    (net (code "261") (name "~{642}") (class "Default")
      (node (ref "DAR4-7") (pin "11") (pinfunction "LD_11") (pintype "input"))
      (node (ref "DAR8-11") (pin "11") (pinfunction "LD_11") (pintype "input"))
      (node (ref "IC29") (pin "11") (pinfunction "Y4_11") (pintype "output"))
    )
    (net (code "262") (name "~{644}") (class "Default")
      (node (ref "IC16") (pin "3") (pinfunction "B_3") (pintype "input"))
      (node (ref "IC25") (pin "11") (pinfunction "Y4_11") (pintype "output"))
    )
    (net (code "263") (name "~{645}") (class "Default")
      (node (ref "IC16") (pin "4") (pinfunction "Y0_4") (pintype "output"))
      (node (ref "IC24") (pin "19") (pinfunction "G_19") (pintype "input"))
      (node (ref "IC31") (pin "19") (pinfunction "G_19") (pintype "input"))
      (node (ref "IC38") (pin "19") (pinfunction "G_19") (pintype "input"))
    )
    (net (code "264") (name "~{ACB00}") (class "Default")
      (node (ref "D34L") (pin "2") (pinfunction "2_2") (pintype "passive"))
      (node (ref "IC37") (pin "12") (pinfunction "Y4_12") (pintype "tri_state"))
      (node (ref "IC38") (pin "12") (pinfunction "Y4_12") (pintype "tri_state"))
      (node (ref "IC38") (pin "3") (pinfunction "Y4_3") (pintype "tri_state"))
    )
    (net (code "265") (name "~{ACB01}") (class "Default")
      (node (ref "D34L") (pin "4") (pinfunction "4_4") (pintype "passive"))
      (node (ref "IC37") (pin "14") (pinfunction "Y3_14") (pintype "tri_state"))
      (node (ref "IC38") (pin "14") (pinfunction "Y3_14") (pintype "tri_state"))
      (node (ref "IC38") (pin "5") (pinfunction "Y3_5") (pintype "tri_state"))
    )
    (net (code "266") (name "~{ACB02}") (class "Default")
      (node (ref "D34L") (pin "6") (pinfunction "6_6") (pintype "passive"))
      (node (ref "IC37") (pin "16") (pinfunction "Y2_16") (pintype "tri_state"))
      (node (ref "IC38") (pin "16") (pinfunction "Y2_16") (pintype "tri_state"))
      (node (ref "IC38") (pin "7") (pinfunction "Y2_7") (pintype "tri_state"))
    )
    (net (code "267") (name "~{ACB03}") (class "Default")
      (node (ref "D34L") (pin "8") (pinfunction "8_8") (pintype "passive"))
      (node (ref "IC37") (pin "18") (pinfunction "Y1_18") (pintype "tri_state"))
      (node (ref "IC38") (pin "18") (pinfunction "Y1_18") (pintype "tri_state"))
      (node (ref "IC38") (pin "9") (pinfunction "Y1_9") (pintype "tri_state"))
    )
    (net (code "268") (name "~{ACB04}") (class "Default")
      (node (ref "D34L") (pin "10") (pinfunction "10_10") (pintype "passive"))
      (node (ref "IC30") (pin "3") (pinfunction "Y4_3") (pintype "tri_state"))
      (node (ref "IC31") (pin "12") (pinfunction "Y4_12") (pintype "tri_state"))
      (node (ref "IC31") (pin "3") (pinfunction "Y4_3") (pintype "tri_state"))
    )
    (net (code "269") (name "~{ACB05}") (class "Default")
      (node (ref "D34L") (pin "12") (pinfunction "12_12") (pintype "passive"))
      (node (ref "IC30") (pin "5") (pinfunction "Y3_5") (pintype "tri_state"))
      (node (ref "IC31") (pin "14") (pinfunction "Y3_14") (pintype "tri_state"))
      (node (ref "IC31") (pin "5") (pinfunction "Y3_5") (pintype "tri_state"))
    )
    (net (code "270") (name "~{ACB06}") (class "Default")
      (node (ref "D34L") (pin "14") (pinfunction "14_14") (pintype "passive"))
      (node (ref "IC30") (pin "7") (pinfunction "Y2_7") (pintype "tri_state"))
      (node (ref "IC31") (pin "16") (pinfunction "Y2_16") (pintype "tri_state"))
      (node (ref "IC31") (pin "7") (pinfunction "Y2_7") (pintype "tri_state"))
    )
    (net (code "271") (name "~{ACB07}") (class "Default")
      (node (ref "D34L") (pin "16") (pinfunction "16_16") (pintype "passive"))
      (node (ref "IC30") (pin "9") (pinfunction "Y1_9") (pintype "tri_state"))
      (node (ref "IC31") (pin "18") (pinfunction "Y1_18") (pintype "tri_state"))
      (node (ref "IC31") (pin "9") (pinfunction "Y1_9") (pintype "tri_state"))
    )
    (net (code "272") (name "~{ACB08}") (class "Default")
      (node (ref "D34L") (pin "18") (pinfunction "18_18") (pintype "passive"))
      (node (ref "IC24") (pin "12") (pinfunction "Y4_12") (pintype "tri_state"))
      (node (ref "IC24") (pin "3") (pinfunction "Y4_3") (pintype "tri_state"))
      (node (ref "IC30") (pin "12") (pinfunction "Y4_12") (pintype "tri_state"))
    )
    (net (code "273") (name "~{ACB09}") (class "Default")
      (node (ref "D34L") (pin "22") (pinfunction "22_22") (pintype "passive"))
      (node (ref "IC24") (pin "14") (pinfunction "Y3_14") (pintype "tri_state"))
      (node (ref "IC24") (pin "5") (pinfunction "Y3_5") (pintype "tri_state"))
      (node (ref "IC30") (pin "14") (pinfunction "Y3_14") (pintype "tri_state"))
    )
    (net (code "274") (name "~{ACB10}") (class "Default")
      (node (ref "D34L") (pin "24") (pinfunction "24_24") (pintype "passive"))
      (node (ref "IC24") (pin "16") (pinfunction "Y2_16") (pintype "tri_state"))
      (node (ref "IC24") (pin "7") (pinfunction "Y2_7") (pintype "tri_state"))
      (node (ref "IC30") (pin "16") (pinfunction "Y2_16") (pintype "tri_state"))
    )
    (net (code "275") (name "~{ACB11}") (class "Default")
      (node (ref "D34L") (pin "26") (pinfunction "26_26") (pintype "passive"))
      (node (ref "IC24") (pin "18") (pinfunction "Y1_18") (pintype "tri_state"))
      (node (ref "IC24") (pin "9") (pinfunction "Y1_9") (pintype "tri_state"))
      (node (ref "IC30") (pin "18") (pinfunction "Y1_18") (pintype "tri_state"))
    )
    (net (code "276") (name "~{ACCLEAR}") (class "Default")
      (node (ref "D34L") (pin "32") (pinfunction "32_32") (pintype "passive"))
      (node (ref "IC22") (pin "12") (pinfunction "O_12") (pintype "open_collector"))
      (node (ref "IC22") (pin "2") (pinfunction "O_2") (pintype "open_collector"))
      (node (ref "IC22") (pin "4") (pinfunction "O_4") (pintype "open_collector"))
    )
    (net (code "277") (name "~{BADDAC}") (class "Default")
      (node (ref "C36L") (pin "34") (pinfunction "34_34") (pintype "passive"))
      (node (ref "IC11") (pin "1") (pinfunction "CLR_1") (pintype "input"))
    )
    (net (code "278") (name "~{BBREAK}") (class "Default")
      (node (ref "C36L") (pin "32") (pinfunction "32_32") (pintype "passive"))
      (node (ref "IC12") (pin "13") (pinfunction "I_13") (pintype "input"))
      (node (ref "IC21") (pin "15") (pinfunction "G_15") (pintype "input"))
      (node (ref "IC26") (pin "1") (pinfunction "G_1") (pintype "input"))
      (node (ref "IC41") (pin "1") (pinfunction "G_1") (pintype "input"))
      (node (ref "IC41") (pin "15") (pinfunction "G_15") (pintype "input"))
      (node (ref "IC6") (pin "1") (pinfunction "G_1") (pintype "input"))
    )
    (net (code "279") (name "~{BINIT}") (class "Default")
      (node (ref "IC10") (pin "1") (pinfunction "CLR_1") (pintype "input"))
      (node (ref "IC10") (pin "13") (pinfunction "CLR_13") (pintype "input"))
      (node (ref "IC12") (pin "2") (pinfunction "O_2") (pintype "output"))
      (node (ref "IC18") (pin "10") (pinfunction "I1_10") (pintype "input"))
      (node (ref "IC18") (pin "13") (pinfunction "I1_13") (pintype "input"))
      (node (ref "IC23") (pin "1") (pinfunction "CLR_1") (pintype "input"))
      (node (ref "IC9") (pin "1") (pinfunction "CLR_1") (pintype "input"))
      (node (ref "IC9") (pin "13") (pinfunction "CLR_13") (pintype "input"))
    )
    (net (code "280") (name "~{BMB03}") (class "Default")
      (node (ref "D35L") (pin "8") (pinfunction "8_8") (pintype "passive"))
    )
    (net (code "281") (name "~{BMB04}") (class "Default")
      (node (ref "D35L") (pin "12") (pinfunction "12_12") (pintype "passive"))
    )
    (net (code "282") (name "~{BMB05}") (class "Default")
      (node (ref "D35L") (pin "16") (pinfunction "16_16") (pintype "passive"))
    )
    (net (code "283") (name "~{BMB06}") (class "Default")
      (node (ref "D35L") (pin "22") (pinfunction "22_22") (pintype "passive"))
    )
    (net (code "284") (name "~{BMB07}") (class "Default")
      (node (ref "D35L") (pin "26") (pinfunction "26_26") (pintype "passive"))
    )
    (net (code "285") (name "~{BMB08}") (class "Default")
      (node (ref "D35L") (pin "30") (pinfunction "30_30") (pintype "passive"))
    )
    (net (code "286") (name "~{BRK_RQ}") (class "Default")
      (node (ref "C36L") (pin "28") (pinfunction "28_28") (pintype "passive"))
      (node (ref "IC11") (pin "6") (pinfunction "~{Q}_6") (pintype "output"))
      (node (ref "SV1") (pin "11") (pinfunction "11_11") (pintype "passive"))
    )
    (net (code "287") (name "~{BRUN}") (class "Default")
      (node (ref "D34L") (pin "34") (pinfunction "34_34") (pintype "passive"))
    )
    (net (code "288") (name "~{BWC0}") (class "Default")
      (node (ref "C35L") (pin "32") (pinfunction "32_32") (pintype "passive"))
      (node (ref "IC18") (pin "4") (pinfunction "I0_4") (pintype "input"))
      (node (ref "SV1") (pin "19") (pinfunction "19_19") (pintype "passive"))
    )
    (net (code "289") (name "~{DA00}") (class "Default")
      (node (ref "C36L") (pin "2") (pinfunction "2_2") (pintype "passive"))
      (node (ref "J14") (pin "1") (pinfunction "1_1") (pintype "passive"))
    )
    (net (code "290") (name "~{DA01}") (class "Default")
      (node (ref "C36L") (pin "4") (pinfunction "4_4") (pintype "passive"))
      (node (ref "J13") (pin "1") (pinfunction "1_1") (pintype "passive"))
    )
    (net (code "291") (name "~{DA02}") (class "Default")
      (node (ref "C36L") (pin "6") (pinfunction "6_6") (pintype "passive"))
      (node (ref "J12") (pin "1") (pinfunction "1_1") (pintype "passive"))
    )
    (net (code "292") (name "~{DA03}") (class "Default")
      (node (ref "C36L") (pin "8") (pinfunction "8_8") (pintype "passive"))
      (node (ref "J11") (pin "1") (pinfunction "1_1") (pintype "passive"))
    )
    (net (code "293") (name "~{DA04}") (class "Default")
      (node (ref "C36L") (pin "10") (pinfunction "10_10") (pintype "passive"))
      (node (ref "J10") (pin "1") (pinfunction "1_1") (pintype "passive"))
    )
    (net (code "294") (name "~{DA05}") (class "Default")
      (node (ref "C36L") (pin "12") (pinfunction "12_12") (pintype "passive"))
      (node (ref "J9") (pin "1") (pinfunction "1_1") (pintype "passive"))
    )
    (net (code "295") (name "~{DA06}") (class "Default")
      (node (ref "C36L") (pin "14") (pinfunction "14_14") (pintype "passive"))
      (node (ref "J8") (pin "1") (pinfunction "1_1") (pintype "passive"))
    )
    (net (code "296") (name "~{DA07}") (class "Default")
      (node (ref "C36L") (pin "16") (pinfunction "16_16") (pintype "passive"))
      (node (ref "J7") (pin "1") (pinfunction "1_1") (pintype "passive"))
    )
    (net (code "297") (name "~{DA08}") (class "Default")
      (node (ref "C36L") (pin "18") (pinfunction "18_18") (pintype "passive"))
      (node (ref "J6") (pin "1") (pinfunction "1_1") (pintype "passive"))
    )
    (net (code "298") (name "~{DA09}") (class "Default")
      (node (ref "C36L") (pin "22") (pinfunction "22_22") (pintype "passive"))
      (node (ref "J5") (pin "1") (pinfunction "1_1") (pintype "passive"))
    )
    (net (code "299") (name "~{DA10}") (class "Default")
      (node (ref "C36L") (pin "24") (pinfunction "24_24") (pintype "passive"))
      (node (ref "J4") (pin "1") (pinfunction "1_1") (pintype "passive"))
    )
    (net (code "300") (name "~{DA11}") (class "Default")
      (node (ref "C36L") (pin "26") (pinfunction "26_26") (pintype "passive"))
      (node (ref "J3") (pin "1") (pinfunction "1_1") (pintype "passive"))
    )
    (net (code "301") (name "~{DATA00}") (class "Default")
      (node (ref "C35L") (pin "2") (pinfunction "2_2") (pintype "passive"))
      (node (ref "IC34") (pin "3") (pinfunction "Y4_3") (pintype "tri_state"))
    )
    (net (code "302") (name "~{DATA01}") (class "Default")
      (node (ref "C35L") (pin "4") (pinfunction "4_4") (pintype "passive"))
      (node (ref "IC34") (pin "5") (pinfunction "Y3_5") (pintype "tri_state"))
    )
    (net (code "303") (name "~{DATA02}") (class "Default")
      (node (ref "C35L") (pin "6") (pinfunction "6_6") (pintype "passive"))
      (node (ref "IC34") (pin "7") (pinfunction "Y2_7") (pintype "tri_state"))
    )
    (net (code "304") (name "~{DATA03}") (class "Default")
      (node (ref "C35L") (pin "8") (pinfunction "8_8") (pintype "passive"))
      (node (ref "IC34") (pin "9") (pinfunction "Y1_9") (pintype "tri_state"))
    )
    (net (code "305") (name "~{DATA04}") (class "Default")
      (node (ref "C35L") (pin "10") (pinfunction "10_10") (pintype "passive"))
      (node (ref "IC34") (pin "12") (pinfunction "Y4_12") (pintype "tri_state"))
    )
    (net (code "306") (name "~{DATA05}") (class "Default")
      (node (ref "C35L") (pin "12") (pinfunction "12_12") (pintype "passive"))
      (node (ref "IC34") (pin "14") (pinfunction "Y3_14") (pintype "tri_state"))
    )
    (net (code "307") (name "~{DATA06}") (class "Default")
      (node (ref "C35L") (pin "14") (pinfunction "14_14") (pintype "passive"))
      (node (ref "IC34") (pin "16") (pinfunction "Y2_16") (pintype "tri_state"))
    )
    (net (code "308") (name "~{DATA07}") (class "Default")
      (node (ref "C35L") (pin "16") (pinfunction "16_16") (pintype "passive"))
      (node (ref "IC34") (pin "18") (pinfunction "Y1_18") (pintype "tri_state"))
    )
    (net (code "309") (name "~{DATA08}") (class "Default")
      (node (ref "C35L") (pin "18") (pinfunction "18_18") (pintype "passive"))
      (node (ref "IC26") (pin "3") (pinfunction "Y4_3") (pintype "tri_state"))
    )
    (net (code "310") (name "~{DATA09}") (class "Default")
      (node (ref "C35L") (pin "22") (pinfunction "22_22") (pintype "passive"))
      (node (ref "IC26") (pin "5") (pinfunction "Y3_5") (pintype "tri_state"))
    )
    (net (code "311") (name "~{DATA10}") (class "Default")
      (node (ref "C35L") (pin "24") (pinfunction "24_24") (pintype "passive"))
      (node (ref "IC26") (pin "7") (pinfunction "Y2_7") (pintype "tri_state"))
    )
    (net (code "312") (name "~{DATA11}") (class "Default")
      (node (ref "C35L") (pin "26") (pinfunction "26_26") (pintype "passive"))
      (node (ref "IC26") (pin "9") (pinfunction "Y1_9") (pintype "tri_state"))
    )
    (net (code "313") (name "~{DCXA}") (class "Default")
      (node (ref "IC16") (pin "12") (pinfunction "Y0_12") (pintype "output"))
      (node (ref "IC18") (pin "9") (pinfunction "I0_9") (pintype "input"))
    )
    (net (code "314") (name "~{DIMA}") (class "Default")
      (node (ref "IC30") (pin "1") (pinfunction "G_1") (pintype "input"))
      (node (ref "IC30") (pin "19") (pinfunction "G_19") (pintype "input"))
      (node (ref "IC37") (pin "1") (pinfunction "G_1") (pintype "input"))
      (node (ref "IC6") (pin "11") (pinfunction "Y1_11") (pintype "output"))
    )
    (net (code "315") (name "~{DIML}") (class "Default")
      (node (ref "FIELD") (pin "11") (pinfunction "LD_11") (pintype "input"))
      (node (ref "IC6") (pin "12") (pinfunction "Y0_12") (pintype "output"))
      (node (ref "INTENB") (pin "11") (pinfunction "LD_11") (pintype "input"))
    )
    (net (code "316") (name "~{DMA-IN}") (class "Default")
      (node (ref "IC12") (pin "11") (pinfunction "I_11") (pintype "input"))
      (node (ref "IC26") (pin "19") (pinfunction "G_19") (pintype "input"))
      (node (ref "IC34") (pin "1") (pinfunction "G_1") (pintype "input"))
      (node (ref "IC34") (pin "19") (pinfunction "G_19") (pintype "input"))
      (node (ref "IC41") (pin "12") (pinfunction "Y0_12") (pintype "output"))
    )
    (net (code "317") (name "~{DMA-OUT}") (class "Default")
      (node (ref "IC28") (pin "1") (pinfunction "G_1") (pintype "input"))
      (node (ref "IC28") (pin "19") (pinfunction "G_19") (pintype "input"))
      (node (ref "IC35") (pin "1") (pinfunction "G_1") (pintype "input"))
      (node (ref "IC35") (pin "19") (pinfunction "G_19") (pintype "input"))
      (node (ref "IC41") (pin "9") (pinfunction "Y3_9") (pintype "output"))
    )
    (net (code "318") (name "~{DRV01}") (class "Default")
      (node (ref "IC41") (pin "4") (pinfunction "Y0_4") (pintype "output"))
      (node (ref "RS08") (pin "38") (pinfunction "38_38") (pintype "passive"))
    )
    (net (code "319") (name "~{DRV23}") (class "Default")
      (node (ref "IC41") (pin "7") (pinfunction "Y3_7") (pintype "output"))
      (node (ref "RS08") (pin "22") (pinfunction "22_22") (pintype "passive"))
    )
    (net (code "320") (name "~{DRVOK}") (class "Default")
      (node (ref "IC21") (pin "13") (pinfunction "B_13") (pintype "input"))
      (node (ref "IC21") (pin "14") (pinfunction "A_14") (pintype "input"))
      (node (ref "R2") (pin "1") (pinfunction "1_1") (pintype "passive"))
      (node (ref "RS08") (pin "40") (pinfunction "40_40") (pintype "passive"))
    )
    (net (code "321") (name "~{ERROR}") (class "Default")
      (node (ref "IC12") (pin "4") (pinfunction "O_4") (pintype "output"))
      (node (ref "IC18") (pin "5") (pinfunction "I1_5") (pintype "input"))
    )
    (net (code "322") (name "~{EXAD0}") (class "Default")
      (node (ref "C35L") (pin "34") (pinfunction "34_34") (pintype "passive"))
      (node (ref "IC26") (pin "18") (pinfunction "Y1_18") (pintype "tri_state"))
    )
    (net (code "323") (name "~{EXAD1}") (class "Default")
      (node (ref "C35L") (pin "36") (pinfunction "36_36") (pintype "passive"))
      (node (ref "IC26") (pin "16") (pinfunction "Y2_16") (pintype "tri_state"))
    )
    (net (code "324") (name "~{EXAD2}") (class "Default")
      (node (ref "C35L") (pin "38") (pinfunction "38_38") (pintype "passive"))
      (node (ref "IC26") (pin "14") (pinfunction "Y3_14") (pintype "tri_state"))
    )
    (net (code "325") (name "~{INT_RQ}") (class "Default")
      (node (ref "D34L") (pin "30") (pinfunction "30_30") (pintype "passive"))
      (node (ref "IC55") (pin "3") (pinfunction "O_3") (pintype "open_collector"))
      (node (ref "IC55") (pin "6") (pinfunction "O_6") (pintype "open_collector"))
      (node (ref "IC55") (pin "8") (pinfunction "O_8") (pintype "open_collector"))
    )
    (net (code "326") (name "~{IOS}") (class "Default")
      (node (ref "D34L") (pin "28") (pinfunction "28_28") (pintype "passive"))
      (node (ref "IC22") (pin "10") (pinfunction "O_10") (pintype "open_collector"))
    )
    (net (code "327") (name "~{MEM_INC}") (class "Default")
      (node (ref "C36L") (pin "36") (pinfunction "36_36") (pintype "passive"))
    )
    (net (code "328") (name "~{MYDEV}") (class "Default")
      (node (ref "IC25") (pin "4") (pinfunction "G2A_4") (pintype "input"))
      (node (ref "IC29") (pin "4") (pinfunction "G2A_4") (pintype "input"))
      (node (ref "IC32") (pin "4") (pinfunction "G2A_4") (pintype "input"))
      (node (ref "PAD1") (pin "1") (pinfunction "P_1") (pintype "passive"))
    )
    (net (code "329") (name "~{NXD}") (class "Default")
      (node (ref "IC23") (pin "6") (pinfunction "~{Q}_6") (pintype "output"))
      (node (ref "IC5") (pin "12") (pinfunction "I2_12") (pintype "input"))
    )
    (net (code "330") (name "~{PER}") (class "Default")
      (node (ref "IC5") (pin "10") (pinfunction "I1_10") (pintype "input"))
      (node (ref "IC5") (pin "9") (pinfunction "I0_9") (pintype "input"))
      (node (ref "IC9") (pin "8") (pinfunction "~{Q}_8") (pintype "output"))
    )
    (net (code "331") (name "~{SETNXD}") (class "Default")
      (node (ref "IC21") (pin "9") (pinfunction "Y3_9") (pintype "output"))
      (node (ref "IC23") (pin "4") (pinfunction "PRE_4") (pintype "input"))
    )
    (net (code "332") (name "~{SETPER}") (class "Default")
      (node (ref "IC13") (pin "5") (pinfunction "EVN_5") (pintype "output"))
      (node (ref "IC9") (pin "10") (pinfunction "PRE_10") (pintype "input"))
    )
    (net (code "333") (name "~{SETWLS}") (class "Default")
      (node (ref "IC6") (pin "7") (pinfunction "Y3_7") (pintype "output"))
      (node (ref "IC9") (pin "4") (pinfunction "PRE_4") (pintype "input"))
    )
    (net (code "334") (name "~{SKIP}") (class "Default")
      (node (ref "IC17") (pin "2") (pinfunction "A_2") (pintype "input"))
      (node (ref "IC19") (pin "10") (pinfunction "O_10") (pintype "open_collector"))
      (node (ref "IC19") (pin "2") (pinfunction "O_2") (pintype "open_collector"))
      (node (ref "IC19") (pin "6") (pinfunction "O_6") (pintype "open_collector"))
      (node (ref "R1") (pin "1") (pinfunction "1_1") (pintype "passive"))
    )
    (net (code "335") (name "~{START}") (class "Default")
      (node (ref "DMA0-3") (pin "11") (pinfunction "LD_11") (pintype "input"))
      (node (ref "DMA4-7") (pin "11") (pinfunction "LD_11") (pintype "input"))
      (node (ref "DMA8-11") (pin "11") (pinfunction "LD_11") (pintype "input"))
      (node (ref "IC10") (pin "10") (pinfunction "PRE_10") (pintype "input"))
      (node (ref "IC12") (pin "6") (pinfunction "O_6") (pintype "output"))
    )
    (net (code "336") (name "~{WE}") (class "Default")
      (node (ref "IC22") (pin "5") (pinfunction "I_5") (pintype "input"))
      (node (ref "IC6") (pin "5") (pinfunction "Y1_5") (pintype "output"))
      (node (ref "RS08") (pin "8") (pinfunction "8_8") (pintype "passive"))
    )
    (net (code "337") (name "~{WLS}") (class "Default")
      (node (ref "IC5") (pin "13") (pinfunction "I3_13") (pintype "input"))
      (node (ref "IC9") (pin "6") (pinfunction "~{Q}_6") (pintype "output"))
    )
  )
)
